# PCB2022-20-02.net
KiCad netlist of a schematic drawn in EAGLE
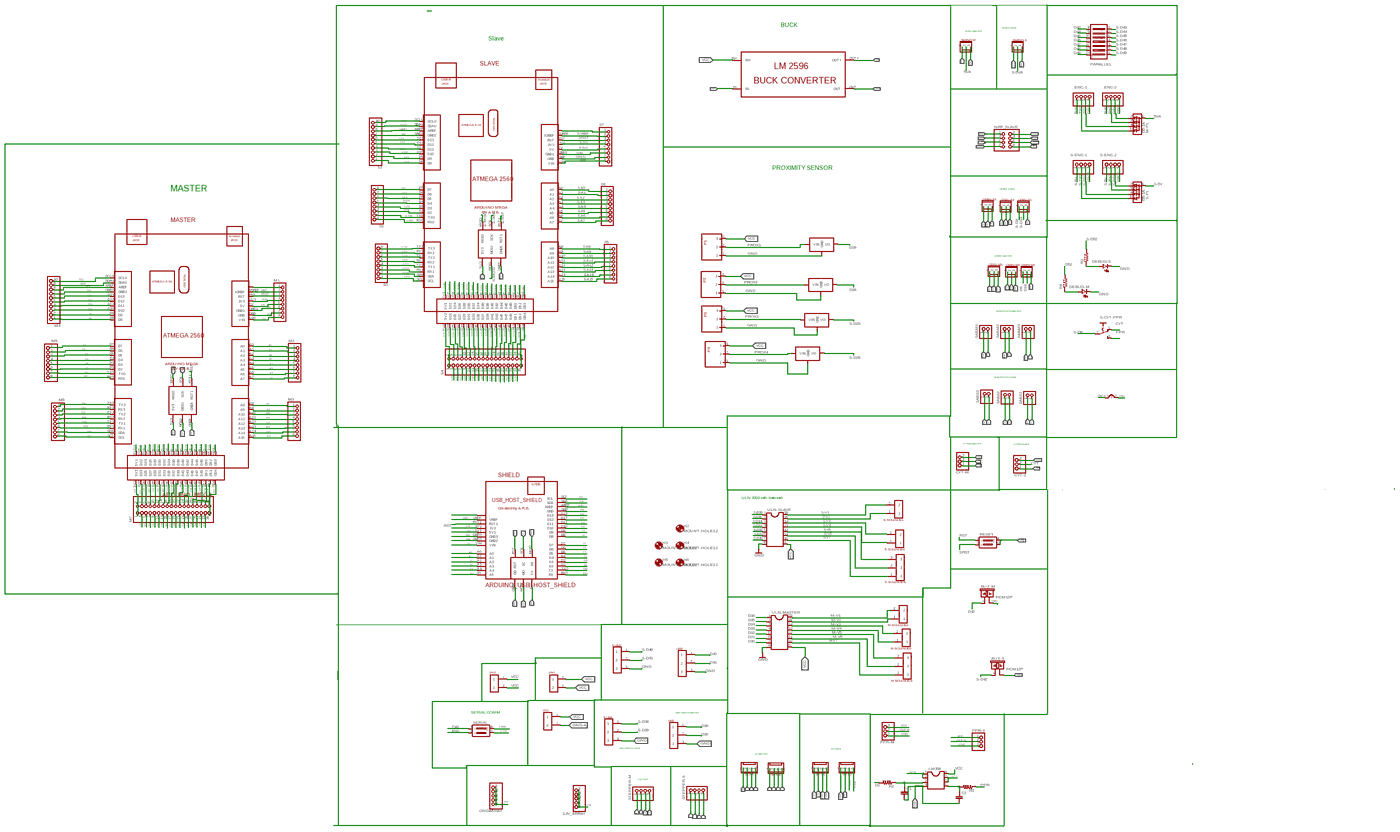
[diagram p0: schematic, sheet 1, overview]
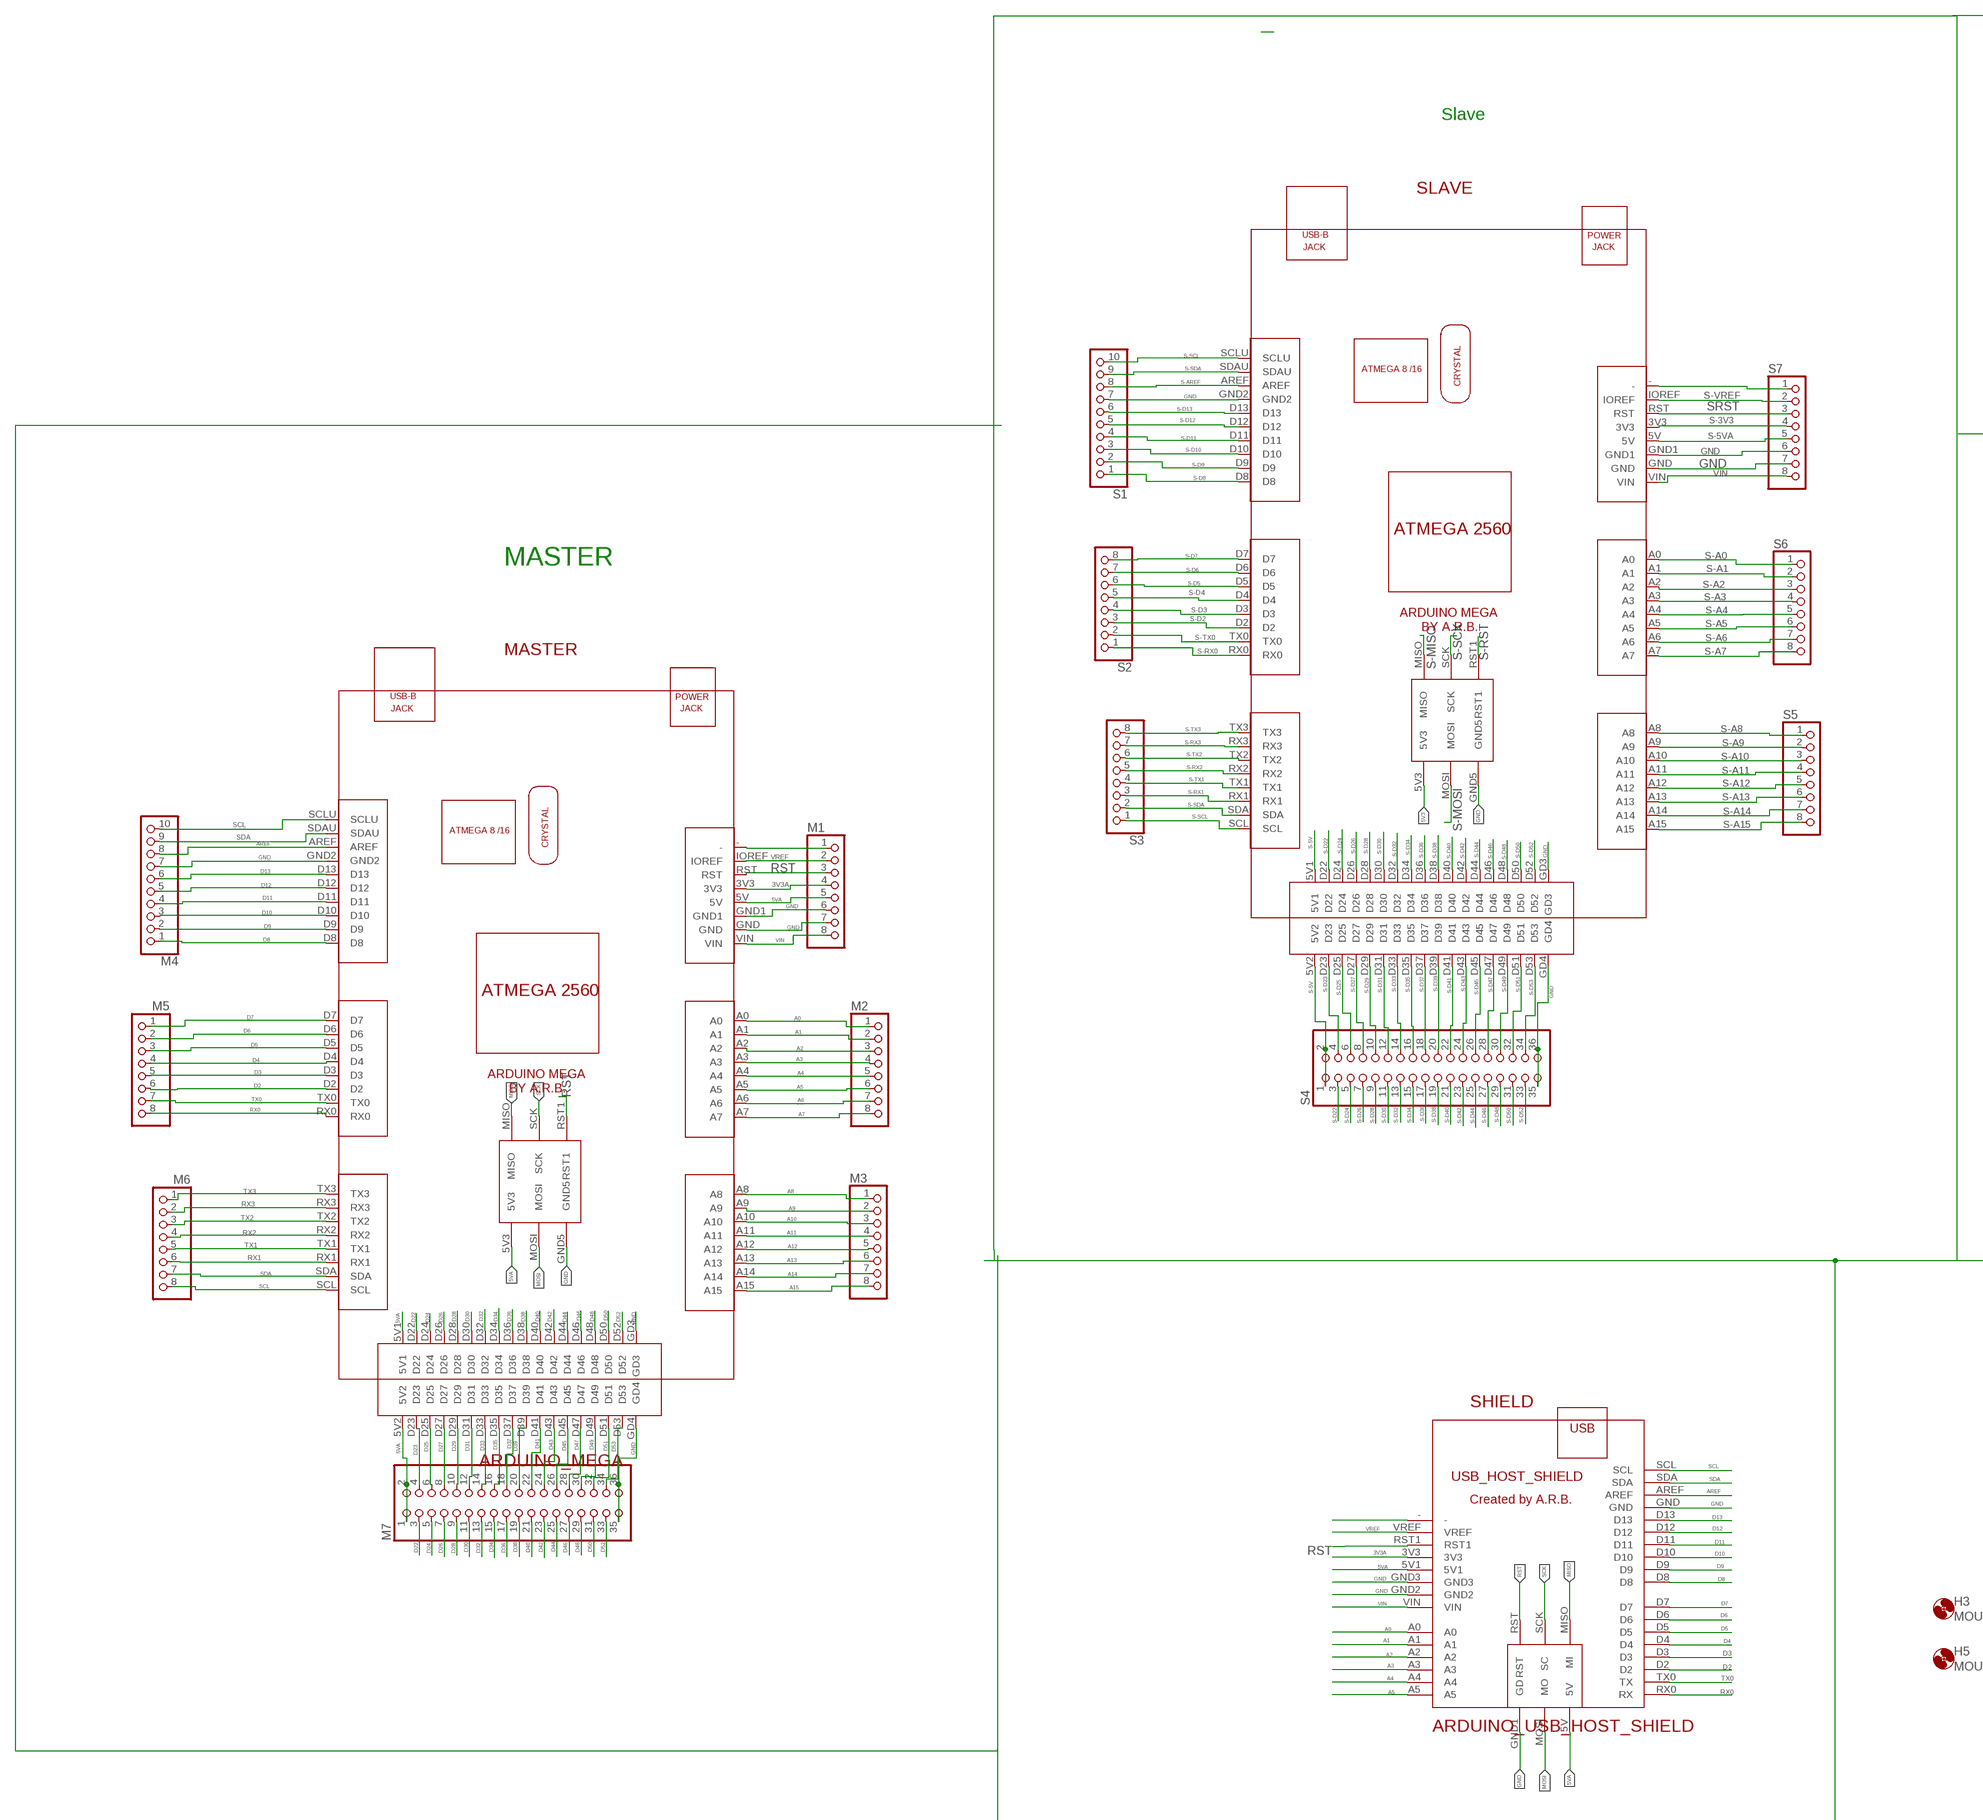
[diagram p1: schematic, sheet 1, part 1 of 4]
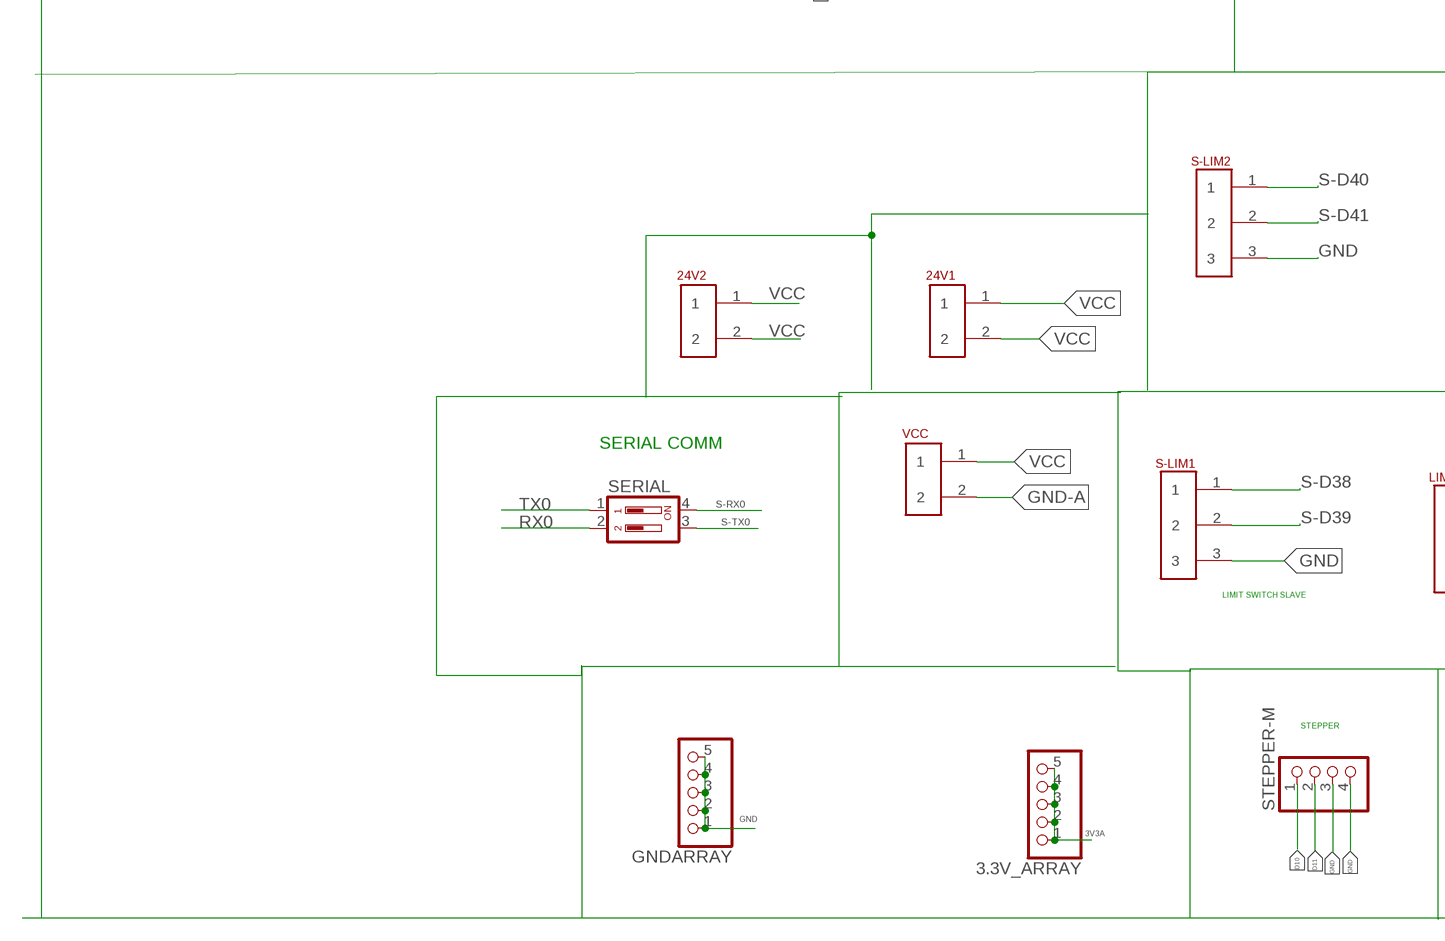
[diagram p2: schematic, sheet 1, part 2 of 4]
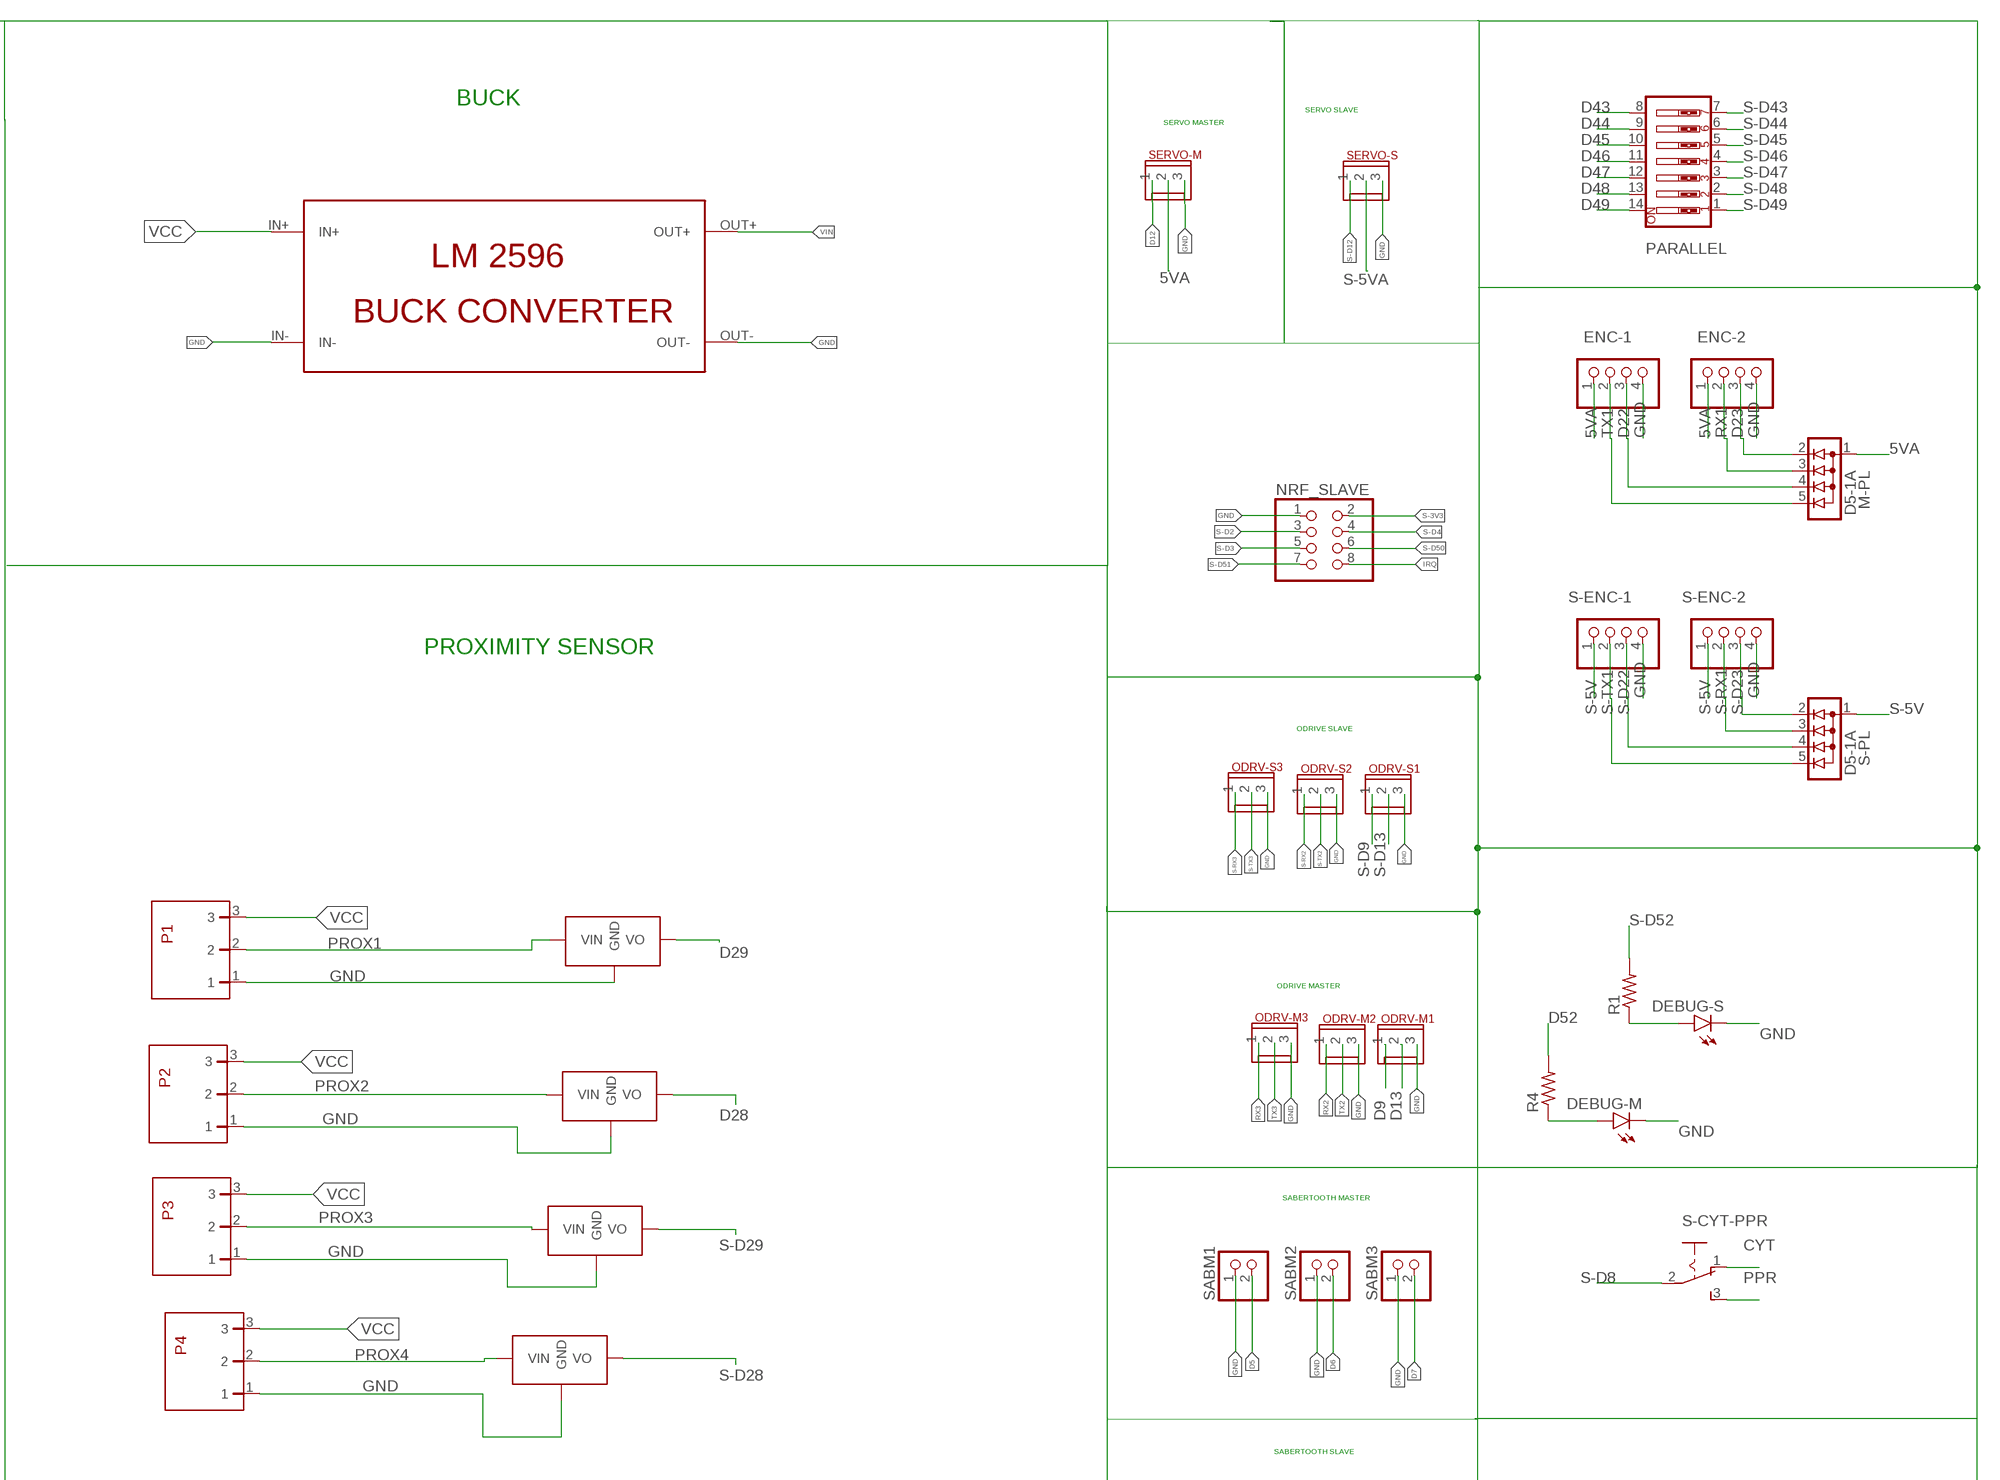
[diagram p3: schematic, sheet 1, part 3 of 4]
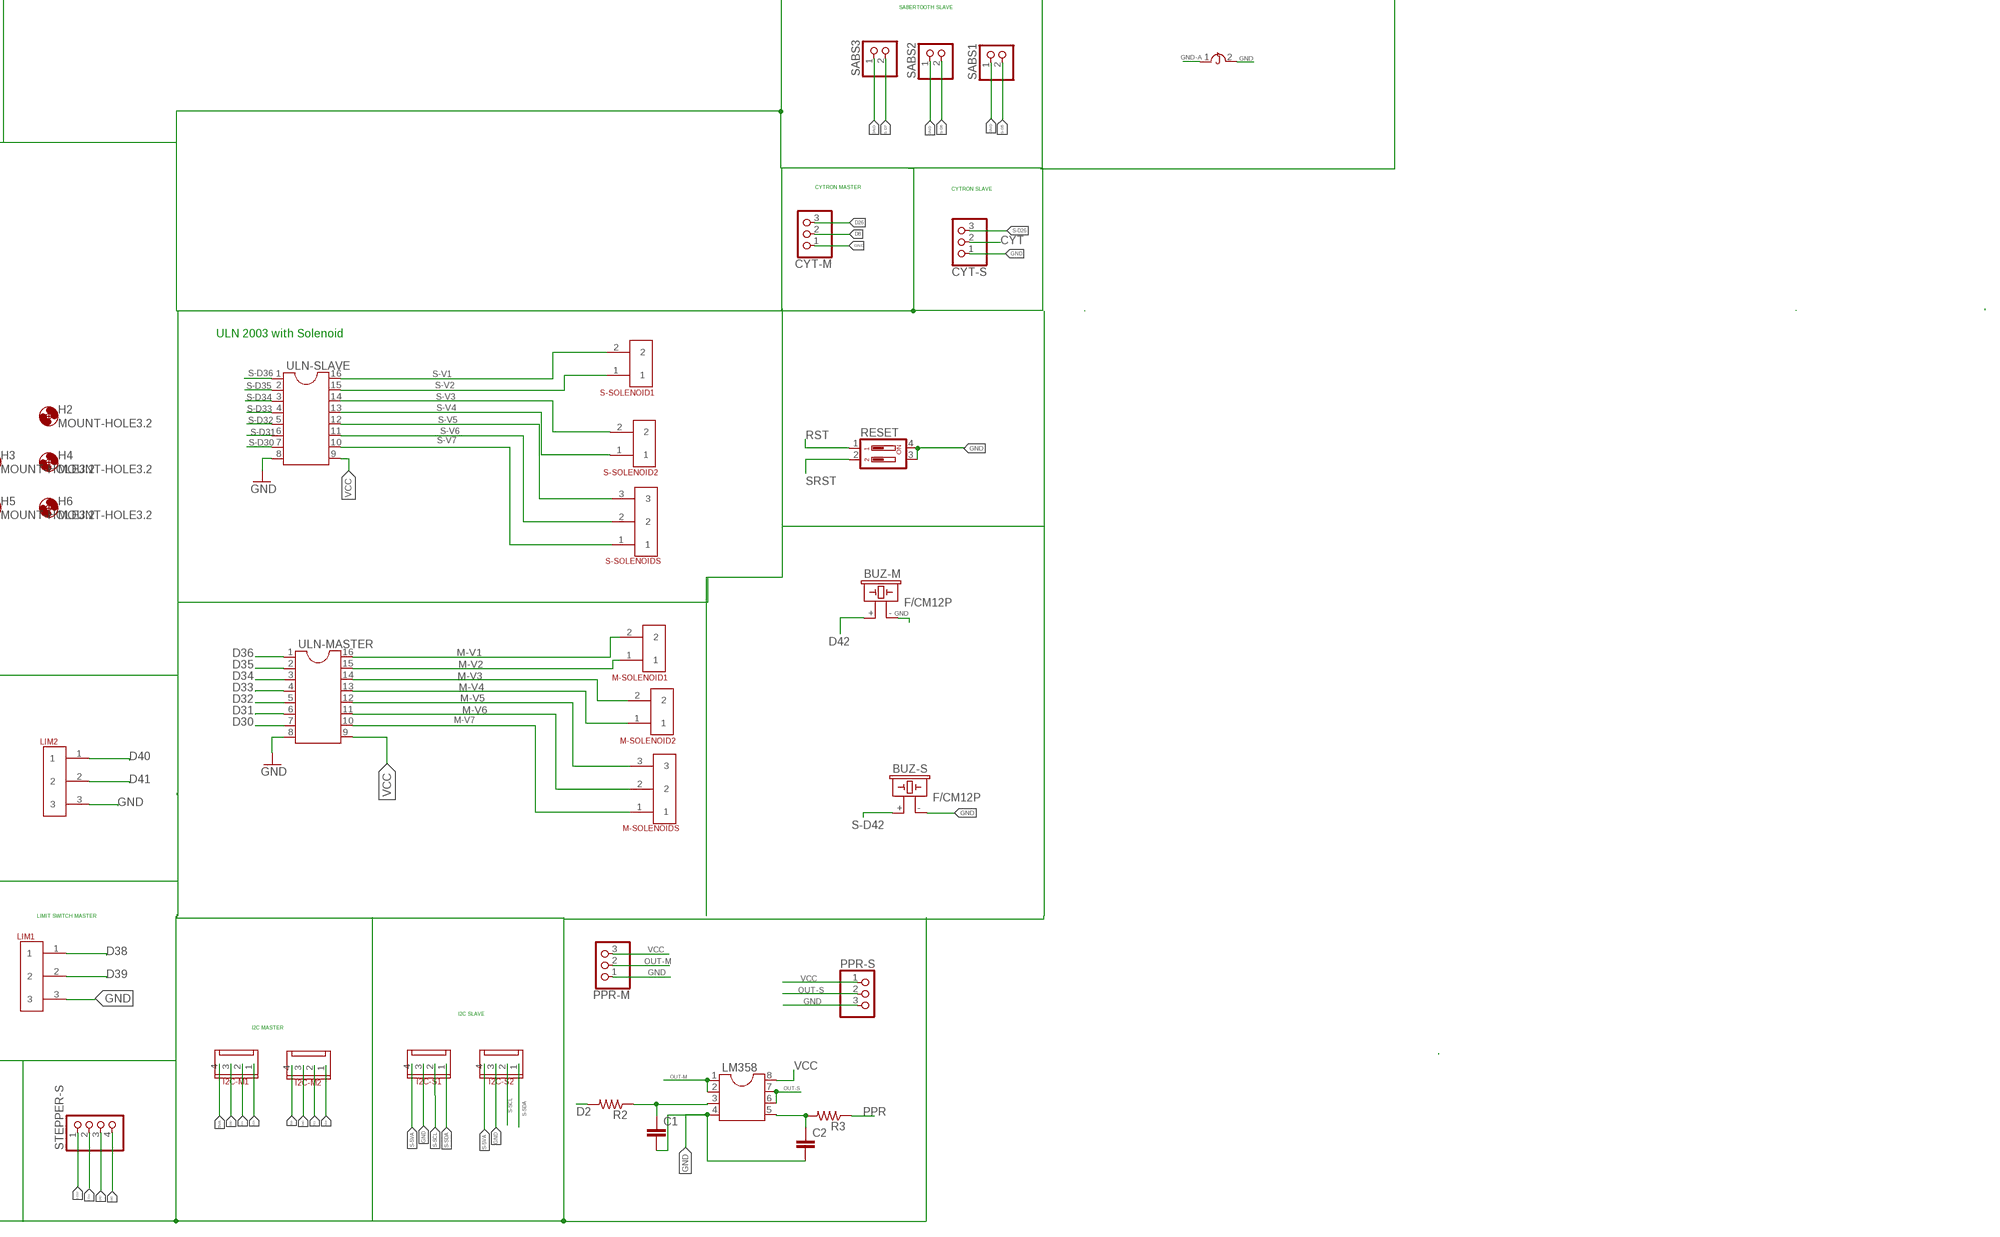
[diagram p4: schematic, sheet 1, part 4 of 4]

(export (version "E")
  (design (tool "Eeschema 10.0.6"))
  (components
    (comp (ref "3.3V_ARRAY")
      (value "PINHD-1X5")
      (footprint "eagle-import:1X05")
      (libsource (lib "eagle-import") (part "PINHD-1X5"))
    )
    (comp (ref "24V1")
      (value "AB_SCREW_TERMINAL_5MM_2PIN")
      (footprint "eagle-import:AB_SCREW_TERMINAL_5MM_2PIN")
      (libsource (lib "eagle-import") (part "AB_SCREW_TERMINAL_5MM_2PIN"))
    )
    (comp (ref "24V2")
      (value "AB_SCREW_TERMINAL_5MM_2PIN")
      (footprint "eagle-import:AB_SCREW_TERMINAL_5MM_2PIN")
      (libsource (lib "eagle-import") (part "AB_SCREW_TERMINAL_5MM_2PIN"))
    )
    (comp (ref "BUZ-M")
      (value "F/CM12P")
      (footprint "eagle-import:F_CM12P")
      (libsource (lib "eagle-import") (part "F/CM12P"))
    )
    (comp (ref "BUZ-S")
      (value "F/CM12P")
      (footprint "eagle-import:F_CM12P")
      (libsource (lib "eagle-import") (part "F/CM12P"))
    )
    (comp (ref "C1")
      (value "C-EU025-025X050")
      (footprint "eagle-import:C025-025X050")
      (libsource (lib "eagle-import") (part "C-EU025-025X050"))
    )
    (comp (ref "C2")
      (value "C-EU025-025X050")
      (footprint "eagle-import:C025-025X050")
      (libsource (lib "eagle-import") (part "C-EU025-025X050"))
    )
    (comp (ref "CYT-M")
      (value "PINHD-1X3")
      (footprint "eagle-import:1X03")
      (libsource (lib "eagle-import") (part "PINHD-1X3"))
    )
    (comp (ref "CYT-S")
      (value "PINHD-1X3")
      (footprint "eagle-import:1X03")
      (libsource (lib "eagle-import") (part "PINHD-1X3"))
    )
    (comp (ref "DEBUG-M")
      (value "LED5MM")
      (footprint "eagle-import:LED5MM")
      (libsource (lib "eagle-import") (part "LED5MM"))
    )
    (comp (ref "DEBUG-S")
      (value "LED5MM")
      (footprint "eagle-import:LED5MM")
      (libsource (lib "eagle-import") (part "LED5MM"))
    )
    (comp (ref "ENC-1")
      (value "PINHD-1X4")
      (footprint "eagle-import:1X04")
      (libsource (lib "eagle-import") (part "PINHD-1X4"))
    )
    (comp (ref "ENC-2")
      (value "PINHD-1X4")
      (footprint "eagle-import:1X04")
      (libsource (lib "eagle-import") (part "PINHD-1X4"))
    )
    (comp (ref "GNDARRAY")
      (value "PINHD-1X5")
      (footprint "eagle-import:1X05")
      (libsource (lib "eagle-import") (part "PINHD-1X5"))
    )
    (comp (ref "H2")
      (value "MOUNT-HOLE3.2")
      (footprint "eagle-import:3,2")
      (libsource (lib "eagle-import") (part "MOUNT-HOLE3.2"))
    )
    (comp (ref "H3")
      (value "MOUNT-HOLE3.2")
      (footprint "eagle-import:3,2")
      (libsource (lib "eagle-import") (part "MOUNT-HOLE3.2"))
    )
    (comp (ref "H4")
      (value "MOUNT-HOLE3.2")
      (footprint "eagle-import:3,2")
      (libsource (lib "eagle-import") (part "MOUNT-HOLE3.2"))
    )
    (comp (ref "H5")
      (value "MOUNT-HOLE3.2")
      (footprint "eagle-import:3,2")
      (libsource (lib "eagle-import") (part "MOUNT-HOLE3.2"))
    )
    (comp (ref "H6")
      (value "MOUNT-HOLE3.2")
      (footprint "eagle-import:3,2")
      (libsource (lib "eagle-import") (part "MOUNT-HOLE3.2"))
    )
    (comp (ref "I2C-M1")
      (value "4PIN_RELIMATE_CONNECTOR")
      (footprint "eagle-import:4PIN_RELIMATE_CONNECTOR")
      (libsource (lib "eagle-import") (part "4PIN_RELIMATE_CONNECTOR"))
    )
    (comp (ref "I2C-M2")
      (value "4PIN_RELIMATE_CONNECTOR")
      (footprint "eagle-import:4PIN_RELIMATE_CONNECTOR")
      (libsource (lib "eagle-import") (part "4PIN_RELIMATE_CONNECTOR"))
    )
    (comp (ref "I2C-S1")
      (value "4PIN_RELIMATE_CONNECTOR")
      (footprint "eagle-import:4PIN_RELIMATE_CONNECTOR")
      (libsource (lib "eagle-import") (part "4PIN_RELIMATE_CONNECTOR"))
    )
    (comp (ref "I2C-S2")
      (value "4PIN_RELIMATE_CONNECTOR")
      (footprint "eagle-import:4PIN_RELIMATE_CONNECTOR")
      (libsource (lib "eagle-import") (part "4PIN_RELIMATE_CONNECTOR"))
    )
    (comp (ref "LIM1")
      (value "AB_SCREW_TER_5MM_3PIN")
      (footprint "eagle-import:AB_SCREW_TER_5MM_3PIN")
      (libsource (lib "eagle-import") (part "AB_SCREW_TER_5MM_3PIN"))
    )
    (comp (ref "LIM2")
      (value "AB_SCREW_TER_5MM_3PIN")
      (footprint "eagle-import:AB_SCREW_TER_5MM_3PIN")
      (libsource (lib "eagle-import") (part "AB_SCREW_TER_5MM_3PIN"))
    )
    (comp (ref "LM358")
      (value "DIL8")
      (footprint "eagle-import:DIL08")
      (libsource (lib "eagle-import") (part "DIL8"))
    )
    (comp (ref "M-PL")
      (value "D5-1A")
      (footprint "eagle-import:SIL05A")
      (libsource (lib "eagle-import") (part "D5-1A"))
    )
    (comp (ref "M-SOLENOID1")
      (value "AB_SCREW_TERMINAL_5MM_2PIN")
      (footprint "eagle-import:AB_SCREW_TERMINAL_5MM_2PIN")
      (libsource (lib "eagle-import") (part "AB_SCREW_TERMINAL_5MM_2PIN"))
    )
    (comp (ref "M-SOLENOID2")
      (value "AB_SCREW_TERMINAL_5MM_2PIN")
      (footprint "eagle-import:AB_SCREW_TERMINAL_5MM_2PIN")
      (libsource (lib "eagle-import") (part "AB_SCREW_TERMINAL_5MM_2PIN"))
    )
    (comp (ref "M-SOLENOIDS")
      (value "AB_SCREW_TER_5MM_3PIN")
      (footprint "eagle-import:AB_SCREW_TER_5MM_3PIN")
      (libsource (lib "eagle-import") (part "AB_SCREW_TER_5MM_3PIN"))
    )
    (comp (ref "M1")
      (value "PINHD-1X8")
      (footprint "eagle-import:1X08")
      (libsource (lib "eagle-import") (part "PINHD-1X8"))
    )
    (comp (ref "M2")
      (value "PINHD-1X8")
      (footprint "eagle-import:1X08")
      (libsource (lib "eagle-import") (part "PINHD-1X8"))
    )
    (comp (ref "M3")
      (value "PINHD-1X8")
      (footprint "eagle-import:1X08")
      (libsource (lib "eagle-import") (part "PINHD-1X8"))
    )
    (comp (ref "M4")
      (value "PINHD-1X10")
      (footprint "eagle-import:1X10")
      (libsource (lib "eagle-import") (part "PINHD-1X10"))
    )
    (comp (ref "M5")
      (value "PINHD-1X8")
      (footprint "eagle-import:1X08")
      (libsource (lib "eagle-import") (part "PINHD-1X8"))
    )
    (comp (ref "M6")
      (value "PINHD-1X8")
      (footprint "eagle-import:1X08")
      (libsource (lib "eagle-import") (part "PINHD-1X8"))
    )
    (comp (ref "M7")
      (value "PINHD-2X18")
      (footprint "eagle-import:2X18")
      (libsource (lib "eagle-import") (part "PINHD-2X18"))
    )
    (comp (ref "MASTER")
      (value "ARDUINO_MEGA")
      (footprint "eagle-import:ARDUINO_MEGA")
      (libsource (lib "eagle-import") (part "ARDUINO_MEGA"))
    )
    (comp (ref "NRF_SLAVE")
      (value "PINHD-2X4")
      (footprint "eagle-import:2X04")
      (libsource (lib "eagle-import") (part "PINHD-2X4"))
    )
    (comp (ref "ODRV-M1")
      (value "3PIN_RELIMATE_CONNECTOR")
      (footprint "eagle-import:3PIN_RELIMATE_CONNECTOR")
      (libsource (lib "eagle-import") (part "3PIN_RELIMATE_CONNECTOR"))
    )
    (comp (ref "ODRV-M2")
      (value "3PIN_RELIMATE_CONNECTOR")
      (footprint "eagle-import:3PIN_RELIMATE_CONNECTOR")
      (libsource (lib "eagle-import") (part "3PIN_RELIMATE_CONNECTOR"))
    )
    (comp (ref "ODRV-M3")
      (value "3PIN_RELIMATE_CONNECTOR")
      (footprint "eagle-import:3PIN_RELIMATE_CONNECTOR")
      (libsource (lib "eagle-import") (part "3PIN_RELIMATE_CONNECTOR"))
    )
    (comp (ref "ODRV-S1")
      (value "3PIN_RELIMATE_CONNECTOR")
      (footprint "eagle-import:3PIN_RELIMATE_CONNECTOR")
      (libsource (lib "eagle-import") (part "3PIN_RELIMATE_CONNECTOR"))
    )
    (comp (ref "ODRV-S2")
      (value "3PIN_RELIMATE_CONNECTOR")
      (footprint "eagle-import:3PIN_RELIMATE_CONNECTOR")
      (libsource (lib "eagle-import") (part "3PIN_RELIMATE_CONNECTOR"))
    )
    (comp (ref "ODRV-S3")
      (value "3PIN_RELIMATE_CONNECTOR")
      (footprint "eagle-import:3PIN_RELIMATE_CONNECTOR")
      (libsource (lib "eagle-import") (part "3PIN_RELIMATE_CONNECTOR"))
    )
    (comp (ref "P1")
      (value "AB_RIGHT_TER_BLK_3PIN")
      (footprint "eagle-import:AB_RIGHT_TER_BLK_3PIN")
      (libsource (lib "eagle-import") (part "AB_RIGHT_TER_BLK_3PIN"))
    )
    (comp (ref "P2")
      (value "AB_RIGHT_TER_BLK_3PIN")
      (footprint "eagle-import:AB_RIGHT_TER_BLK_3PIN")
      (libsource (lib "eagle-import") (part "AB_RIGHT_TER_BLK_3PIN"))
    )
    (comp (ref "P3")
      (value "AB_RIGHT_TER_BLK_3PIN")
      (footprint "eagle-import:AB_RIGHT_TER_BLK_3PIN")
      (libsource (lib "eagle-import") (part "AB_RIGHT_TER_BLK_3PIN"))
    )
    (comp (ref "P4")
      (value "AB_RIGHT_TER_BLK_3PIN")
      (footprint "eagle-import:AB_RIGHT_TER_BLK_3PIN")
      (libsource (lib "eagle-import") (part "AB_RIGHT_TER_BLK_3PIN"))
    )
    (comp (ref "PARALLEL")
      (value "SW_DIP-7")
      (footprint "eagle-import:EDG-07")
      (libsource (lib "eagle-import") (part "SW_DIP-7"))
    )
    (comp (ref "PPR-M")
      (value "PINHD-1X3")
      (footprint "eagle-import:1X03")
      (libsource (lib "eagle-import") (part "PINHD-1X3"))
    )
    (comp (ref "PPR-S")
      (value "PINHD-1X3")
      (footprint "eagle-import:1X03")
      (libsource (lib "eagle-import") (part "PINHD-1X3"))
    )
    (comp (ref "R1")
      (value "R-US_0204/5")
      (footprint "eagle-import:0204_5")
      (libsource (lib "eagle-import") (part "R-US_0204/5"))
    )
    (comp (ref "R2")
      (value "R-US_0204/5")
      (footprint "eagle-import:0204_5")
      (libsource (lib "eagle-import") (part "R-US_0204/5"))
    )
    (comp (ref "R3")
      (value "R-US_0204/5")
      (footprint "eagle-import:0204_5")
      (libsource (lib "eagle-import") (part "R-US_0204/5"))
    )
    (comp (ref "R4")
      (value "R-US_0204/5")
      (footprint "eagle-import:0204_5")
      (libsource (lib "eagle-import") (part "R-US_0204/5"))
    )
    (comp (ref "RESET")
      (value "DIP02YL")
      (footprint "eagle-import:DIP02YL")
      (libsource (lib "eagle-import") (part "DIP02YL"))
    )
    (comp (ref "S-CYT-PPR")
      (value "255SB")
      (footprint "eagle-import:255SB")
      (libsource (lib "eagle-import") (part "255SB"))
    )
    (comp (ref "S-ENC-1")
      (value "PINHD-1X4")
      (footprint "eagle-import:1X04")
      (libsource (lib "eagle-import") (part "PINHD-1X4"))
    )
    (comp (ref "S-ENC-2")
      (value "PINHD-1X4")
      (footprint "eagle-import:1X04")
      (libsource (lib "eagle-import") (part "PINHD-1X4"))
    )
    (comp (ref "S-LIM1")
      (value "AB_SCREW_TER_5MM_3PIN")
      (footprint "eagle-import:AB_SCREW_TER_5MM_3PIN")
      (libsource (lib "eagle-import") (part "AB_SCREW_TER_5MM_3PIN"))
    )
    (comp (ref "S-LIM2")
      (value "AB_SCREW_TER_5MM_3PIN")
      (footprint "eagle-import:AB_SCREW_TER_5MM_3PIN")
      (libsource (lib "eagle-import") (part "AB_SCREW_TER_5MM_3PIN"))
    )
    (comp (ref "S-PL")
      (value "D5-1A")
      (footprint "eagle-import:SIL05A")
      (libsource (lib "eagle-import") (part "D5-1A"))
    )
    (comp (ref "S-SOLENOID1")
      (value "AB_SCREW_TERMINAL_5MM_2PIN")
      (footprint "eagle-import:AB_SCREW_TERMINAL_5MM_2PIN")
      (libsource (lib "eagle-import") (part "AB_SCREW_TERMINAL_5MM_2PIN"))
    )
    (comp (ref "S-SOLENOID2")
      (value "AB_SCREW_TERMINAL_5MM_2PIN")
      (footprint "eagle-import:AB_SCREW_TERMINAL_5MM_2PIN")
      (libsource (lib "eagle-import") (part "AB_SCREW_TERMINAL_5MM_2PIN"))
    )
    (comp (ref "S-SOLENOIDS")
      (value "AB_SCREW_TER_5MM_3PIN")
      (footprint "eagle-import:AB_SCREW_TER_5MM_3PIN")
      (libsource (lib "eagle-import") (part "AB_SCREW_TER_5MM_3PIN"))
    )
    (comp (ref "S1")
      (value "PINHD-1X10")
      (footprint "eagle-import:1X10")
      (libsource (lib "eagle-import") (part "PINHD-1X10"))
    )
    (comp (ref "S2")
      (value "PINHD-1X8")
      (footprint "eagle-import:1X08")
      (libsource (lib "eagle-import") (part "PINHD-1X8"))
    )
    (comp (ref "S3")
      (value "PINHD-1X8")
      (footprint "eagle-import:1X08")
      (libsource (lib "eagle-import") (part "PINHD-1X8"))
    )
    (comp (ref "S4")
      (value "PINHD-2X18")
      (footprint "eagle-import:2X18")
      (libsource (lib "eagle-import") (part "PINHD-2X18"))
    )
    (comp (ref "S5")
      (value "PINHD-1X8")
      (footprint "eagle-import:1X08")
      (libsource (lib "eagle-import") (part "PINHD-1X8"))
    )
    (comp (ref "S6")
      (value "PINHD-1X8")
      (footprint "eagle-import:1X08")
      (libsource (lib "eagle-import") (part "PINHD-1X8"))
    )
    (comp (ref "S7")
      (value "PINHD-1X8")
      (footprint "eagle-import:1X08")
      (libsource (lib "eagle-import") (part "PINHD-1X8"))
    )
    (comp (ref "SABM1")
      (value "PINHD-1X2")
      (footprint "eagle-import:1X02")
      (fields (field (name "SPICEPREFIX") "B"))
      (libsource (lib "eagle-import") (part "PINHD-1X2"))
    )
    (comp (ref "SABM2")
      (value "PINHD-1X2")
      (footprint "eagle-import:1X02")
      (libsource (lib "eagle-import") (part "PINHD-1X2"))
    )
    (comp (ref "SABM3")
      (value "PINHD-1X2")
      (footprint "eagle-import:1X02")
      (libsource (lib "eagle-import") (part "PINHD-1X2"))
    )
    (comp (ref "SABS1")
      (value "PINHD-1X2")
      (footprint "eagle-import:1X02")
      (libsource (lib "eagle-import") (part "PINHD-1X2"))
    )
    (comp (ref "SABS2")
      (value "PINHD-1X2")
      (footprint "eagle-import:1X02")
      (libsource (lib "eagle-import") (part "PINHD-1X2"))
    )
    (comp (ref "SABS3")
      (value "PINHD-1X2")
      (footprint "eagle-import:1X02")
      (libsource (lib "eagle-import") (part "PINHD-1X2"))
    )
    (comp (ref "SERIAL")
      (value "DIP02YL")
      (footprint "eagle-import:DIP02YL")
      (libsource (lib "eagle-import") (part "DIP02YL"))
    )
    (comp (ref "SERVO-M")
      (value "3PIN_RELIMATE_CONNECTOR")
      (footprint "eagle-import:3PIN_RELIMATE_CONNECTOR")
      (libsource (lib "eagle-import") (part "3PIN_RELIMATE_CONNECTOR"))
    )
    (comp (ref "SERVO-S")
      (value "3PIN_RELIMATE_CONNECTOR")
      (footprint "eagle-import:3PIN_RELIMATE_CONNECTOR")
      (libsource (lib "eagle-import") (part "3PIN_RELIMATE_CONNECTOR"))
    )
    (comp (ref "SHIELD")
      (value "ARDUINO_USB_HOST_SHIELD")
      (footprint "eagle-import:ARDUINO_USB_HOST_SHIELD")
      (libsource (lib "eagle-import") (part "ARDUINO_USB_HOST_SHIELD"))
    )
    (comp (ref "SLAVE")
      (value "ARDUINO_MEGA")
      (footprint "eagle-import:ARDUINO_MEGA")
      (libsource (lib "eagle-import") (part "ARDUINO_MEGA"))
    )
    (comp (ref "STEPPER-M")
      (value "PINHD-1X4")
      (footprint "eagle-import:1X04")
      (libsource (lib "eagle-import") (part "PINHD-1X4"))
    )
    (comp (ref "STEPPER-S")
      (value "PINHD-1X4")
      (footprint "eagle-import:1X04")
      (libsource (lib "eagle-import") (part "PINHD-1X4"))
    )
    (comp (ref "U$2")
      (value "AB_JUMPER_ONE_WAY")
      (footprint "eagle-import:AB_JUMPER_ONE_WAY")
      (libsource (lib "eagle-import") (part "AB_JUMPER_ONE_WAY"))
    )
    (comp (ref "U$3")
      (value "LM2596_BUCK_CONVERTER")
      (footprint "eagle-import:LM2596_BUCK_CONVERTER")
      (libsource (lib "eagle-import") (part "LM2596_BUCK_CONVERTER"))
    )
    (comp (ref "U$10")
      (value "AB_7805_FLAT")
      (footprint "eagle-import:AB_7805_FLAT")
      (libsource (lib "eagle-import") (part "AB_7805_FLAT"))
    )
    (comp (ref "U$11")
      (value "AB_7805_FLAT")
      (footprint "eagle-import:AB_7805_FLAT")
      (libsource (lib "eagle-import") (part "AB_7805_FLAT"))
    )
    (comp (ref "U$12")
      (value "AB_7805_FLAT")
      (footprint "eagle-import:AB_7805_FLAT")
      (libsource (lib "eagle-import") (part "AB_7805_FLAT"))
    )
    (comp (ref "U$13")
      (value "AB_7805_FLAT")
      (footprint "eagle-import:AB_7805_FLAT")
      (libsource (lib "eagle-import") (part "AB_7805_FLAT"))
    )
    (comp (ref "ULN-MASTER")
      (value "DIL16")
      (footprint "eagle-import:DIL16")
      (libsource (lib "eagle-import") (part "DIL16"))
    )
    (comp (ref "ULN-SLAVE")
      (value "DIL16")
      (footprint "eagle-import:DIL16")
      (libsource (lib "eagle-import") (part "DIL16"))
    )
    (comp (ref "VCC")
      (value "AB_SCREW_TERMINAL_5MM_2PIN")
      (footprint "eagle-import:AB_SCREW_TERMINAL_5MM_2PIN")
      (libsource (lib "eagle-import") (part "AB_SCREW_TERMINAL_5MM_2PIN"))
    )
  )
  (nets
    (net (code "1") (name "/3V3A") (class "Default")
      (node (ref "3.3V_ARRAY") (pin "1") (pinfunction "1_1") (pintype "passive"))
      (node (ref "3.3V_ARRAY") (pin "2") (pinfunction "2_2") (pintype "passive"))
      (node (ref "3.3V_ARRAY") (pin "3") (pinfunction "3_3") (pintype "passive"))
      (node (ref "3.3V_ARRAY") (pin "4") (pinfunction "4_4") (pintype "passive"))
      (node (ref "3.3V_ARRAY") (pin "5") (pinfunction "5_5") (pintype "passive"))
      (node (ref "M1") (pin "4") (pinfunction "4_4") (pintype "passive"))
      (node (ref "MASTER") (pin "3V3") (pinfunction "3V3_3V3") (pintype "bidirectional"))
      (node (ref "SHIELD") (pin "3V3") (pinfunction "3V3_3V3") (pintype "bidirectional"))
    )
    (net (code "2") (name "/A0") (class "Default")
      (node (ref "M2") (pin "1") (pinfunction "1_1") (pintype "passive"))
      (node (ref "MASTER") (pin "A0") (pinfunction "A0_A0") (pintype "bidirectional"))
      (node (ref "SHIELD") (pin "A0") (pinfunction "A0_A0") (pintype "bidirectional"))
    )
    (net (code "3") (name "/A1") (class "Default")
      (node (ref "M2") (pin "2") (pinfunction "2_2") (pintype "passive"))
      (node (ref "MASTER") (pin "A1") (pinfunction "A1_A1") (pintype "bidirectional"))
      (node (ref "SHIELD") (pin "A1") (pinfunction "A1_A1") (pintype "bidirectional"))
    )
    (net (code "4") (name "/A2") (class "Default")
      (node (ref "M2") (pin "3") (pinfunction "3_3") (pintype "passive"))
      (node (ref "MASTER") (pin "A2") (pinfunction "A2_A2") (pintype "bidirectional"))
      (node (ref "SHIELD") (pin "A2") (pinfunction "A2_A2") (pintype "bidirectional"))
    )
    (net (code "5") (name "/A3") (class "Default")
      (node (ref "M2") (pin "4") (pinfunction "4_4") (pintype "passive"))
      (node (ref "MASTER") (pin "A3") (pinfunction "A3_A3") (pintype "bidirectional"))
      (node (ref "SHIELD") (pin "A3") (pinfunction "A3_A3") (pintype "bidirectional"))
    )
    (net (code "6") (name "/A4") (class "Default")
      (node (ref "M2") (pin "5") (pinfunction "5_5") (pintype "passive"))
      (node (ref "MASTER") (pin "A4") (pinfunction "A4_A4") (pintype "bidirectional"))
      (node (ref "SHIELD") (pin "A4") (pinfunction "A4_A4") (pintype "bidirectional"))
    )
    (net (code "7") (name "/A5") (class "Default")
      (node (ref "M2") (pin "6") (pinfunction "6_6") (pintype "passive"))
      (node (ref "MASTER") (pin "A5") (pinfunction "A5_A5") (pintype "bidirectional"))
      (node (ref "SHIELD") (pin "A5") (pinfunction "A5_A5") (pintype "bidirectional"))
    )
    (net (code "8") (name "/A6") (class "Default")
      (node (ref "M2") (pin "7") (pinfunction "7_7") (pintype "passive"))
      (node (ref "MASTER") (pin "A6") (pinfunction "A6_A6") (pintype "bidirectional"))
    )
    (net (code "9") (name "/A7") (class "Default")
      (node (ref "M2") (pin "8") (pinfunction "8_8") (pintype "passive"))
      (node (ref "MASTER") (pin "A7") (pinfunction "A7_A7") (pintype "bidirectional"))
    )
    (net (code "10") (name "/A8") (class "Default")
      (node (ref "M3") (pin "1") (pinfunction "1_1") (pintype "passive"))
      (node (ref "MASTER") (pin "A8") (pinfunction "A8_A8") (pintype "bidirectional"))
    )
    (net (code "11") (name "/A9") (class "Default")
      (node (ref "M3") (pin "2") (pinfunction "2_2") (pintype "passive"))
      (node (ref "MASTER") (pin "A9") (pinfunction "A9_A9") (pintype "bidirectional"))
    )
    (net (code "12") (name "/A10") (class "Default")
      (node (ref "M3") (pin "3") (pinfunction "3_3") (pintype "passive"))
      (node (ref "MASTER") (pin "A10") (pinfunction "A10_A10") (pintype "bidirectional"))
    )
    (net (code "13") (name "/A11") (class "Default")
      (node (ref "M3") (pin "4") (pinfunction "4_4") (pintype "passive"))
      (node (ref "MASTER") (pin "A11") (pinfunction "A11_A11") (pintype "bidirectional"))
    )
    (net (code "14") (name "/A12") (class "Default")
      (node (ref "M3") (pin "5") (pinfunction "5_5") (pintype "passive"))
      (node (ref "MASTER") (pin "A12") (pinfunction "A12_A12") (pintype "bidirectional"))
    )
    (net (code "15") (name "/A13") (class "Default")
      (node (ref "M3") (pin "6") (pinfunction "6_6") (pintype "passive"))
      (node (ref "MASTER") (pin "A13") (pinfunction "A13_A13") (pintype "bidirectional"))
    )
    (net (code "16") (name "/A14") (class "Default")
      (node (ref "M3") (pin "7") (pinfunction "7_7") (pintype "passive"))
      (node (ref "MASTER") (pin "A14") (pinfunction "A14_A14") (pintype "bidirectional"))
    )
    (net (code "17") (name "/A15") (class "Default")
      (node (ref "M3") (pin "8") (pinfunction "8_8") (pintype "passive"))
      (node (ref "MASTER") (pin "A15") (pinfunction "A15_A15") (pintype "bidirectional"))
    )
    (net (code "18") (name "/AREF") (class "Default")
      (node (ref "M4") (pin "8") (pinfunction "8_8") (pintype "passive"))
      (node (ref "MASTER") (pin "AREF") (pinfunction "AREF_AREF") (pintype "bidirectional"))
      (node (ref "SHIELD") (pin "AREF") (pinfunction "AREF_AREF") (pintype "bidirectional"))
    )
    (net (code "19") (name "/CYT") (class "Default")
      (node (ref "CYT-S") (pin "2") (pinfunction "2_2") (pintype "passive"))
      (node (ref "S-CYT-PPR") (pin "1") (pinfunction "O_1") (pintype "passive"))
    )
    (net (code "20") (name "/D2") (class "Default")
      (node (ref "M5") (pin "6") (pinfunction "6_6") (pintype "passive"))
      (node (ref "MASTER") (pin "D2") (pinfunction "D2_D2") (pintype "bidirectional"))
      (node (ref "R2") (pin "2") (pinfunction "2_2") (pintype "passive"))
      (node (ref "SHIELD") (pin "D2") (pinfunction "D2_D2") (pintype "bidirectional"))
    )
    (net (code "21") (name "/D3") (class "Default")
      (node (ref "M5") (pin "5") (pinfunction "5_5") (pintype "passive"))
      (node (ref "MASTER") (pin "D3") (pinfunction "D3_D3") (pintype "bidirectional"))
      (node (ref "SHIELD") (pin "D3") (pinfunction "D3_D3") (pintype "bidirectional"))
    )
    (net (code "22") (name "/D4") (class "Default")
      (node (ref "M5") (pin "4") (pinfunction "4_4") (pintype "passive"))
      (node (ref "MASTER") (pin "D4") (pinfunction "D4_D4") (pintype "bidirectional"))
      (node (ref "SHIELD") (pin "D4") (pinfunction "D4_D4") (pintype "bidirectional"))
    )
    (net (code "23") (name "/D9") (class "Default")
      (node (ref "M4") (pin "2") (pinfunction "2_2") (pintype "passive"))
      (node (ref "MASTER") (pin "D9") (pinfunction "D9_D9") (pintype "bidirectional"))
      (node (ref "ODRV-M1") (pin "1") (pinfunction "1_1") (pintype "bidirectional"))
      (node (ref "SHIELD") (pin "D9") (pinfunction "D9_D9") (pintype "bidirectional"))
    )
    (net (code "24") (name "/D13") (class "Default")
      (node (ref "M4") (pin "6") (pinfunction "6_6") (pintype "passive"))
      (node (ref "MASTER") (pin "D13") (pinfunction "D13_D13") (pintype "bidirectional"))
      (node (ref "ODRV-M1") (pin "2") (pinfunction "2_2") (pintype "bidirectional"))
      (node (ref "SHIELD") (pin "D13") (pinfunction "D13_D13") (pintype "bidirectional"))
    )
    (net (code "25") (name "/D22") (class "Default")
      (node (ref "ENC-1") (pin "3") (pinfunction "3_3") (pintype "passive"))
      (node (ref "M-PL") (pin "4") (pinfunction "C4_4") (pintype "passive"))
      (node (ref "M7") (pin "3") (pinfunction "3_3") (pintype "passive"))
      (node (ref "MASTER") (pin "D22") (pinfunction "D22_D22") (pintype "bidirectional"))
    )
    (net (code "26") (name "/D23") (class "Default")
      (node (ref "ENC-2") (pin "3") (pinfunction "3_3") (pintype "passive"))
      (node (ref "M-PL") (pin "2") (pinfunction "C2_2") (pintype "passive"))
      (node (ref "M7") (pin "4") (pinfunction "4_4") (pintype "passive"))
      (node (ref "MASTER") (pin "D23") (pinfunction "D23_D23") (pintype "bidirectional"))
    )
    (net (code "27") (name "/D24") (class "Default")
      (node (ref "M7") (pin "5") (pinfunction "5_5") (pintype "passive"))
      (node (ref "MASTER") (pin "D24") (pinfunction "D24_D24") (pintype "bidirectional"))
    )
    (net (code "28") (name "/D25") (class "Default")
      (node (ref "M7") (pin "6") (pinfunction "6_6") (pintype "passive"))
      (node (ref "MASTER") (pin "D25") (pinfunction "D25_D25") (pintype "bidirectional"))
    )
    (net (code "29") (name "/D27") (class "Default")
      (node (ref "M7") (pin "8") (pinfunction "8_8") (pintype "passive"))
      (node (ref "MASTER") (pin "D27") (pinfunction "D27_D27") (pintype "bidirectional"))
    )
    (net (code "30") (name "/D28") (class "Default")
      (node (ref "M7") (pin "9") (pinfunction "9_9") (pintype "passive"))
      (node (ref "MASTER") (pin "D28") (pinfunction "D28_D28") (pintype "bidirectional"))
      (node (ref "U$11") (pin "3") (pinfunction "VO_3") (pintype "bidirectional"))
    )
    (net (code "31") (name "/D29") (class "Default")
      (node (ref "M7") (pin "10") (pinfunction "10_10") (pintype "passive"))
      (node (ref "MASTER") (pin "D29") (pinfunction "D29_D29") (pintype "bidirectional"))
      (node (ref "U$10") (pin "3") (pinfunction "VO_3") (pintype "bidirectional"))
    )
    (net (code "32") (name "/D30") (class "Default")
      (node (ref "M7") (pin "11") (pinfunction "11_11") (pintype "passive"))
      (node (ref "MASTER") (pin "D30") (pinfunction "D30_D30") (pintype "bidirectional"))
      (node (ref "ULN-MASTER") (pin "7") (pinfunction "7_7") (pintype "passive"))
    )
    (net (code "33") (name "/D31") (class "Default")
      (node (ref "M7") (pin "12") (pinfunction "12_12") (pintype "passive"))
      (node (ref "MASTER") (pin "D31") (pinfunction "D31_D31") (pintype "bidirectional"))
      (node (ref "ULN-MASTER") (pin "6") (pinfunction "6_6") (pintype "passive"))
    )
    (net (code "34") (name "/D32") (class "Default")
      (node (ref "M7") (pin "13") (pinfunction "13_13") (pintype "passive"))
      (node (ref "MASTER") (pin "D32") (pinfunction "D32_D32") (pintype "bidirectional"))
      (node (ref "ULN-MASTER") (pin "5") (pinfunction "5_5") (pintype "passive"))
    )
    (net (code "35") (name "/D33") (class "Default")
      (node (ref "M7") (pin "14") (pinfunction "14_14") (pintype "passive"))
      (node (ref "MASTER") (pin "D33") (pinfunction "D33_D33") (pintype "bidirectional"))
      (node (ref "ULN-MASTER") (pin "4") (pinfunction "4_4") (pintype "passive"))
    )
    (net (code "36") (name "/D34") (class "Default")
      (node (ref "M7") (pin "15") (pinfunction "15_15") (pintype "passive"))
      (node (ref "MASTER") (pin "D34") (pinfunction "D34_D34") (pintype "bidirectional"))
      (node (ref "ULN-MASTER") (pin "3") (pinfunction "3_3") (pintype "passive"))
    )
    (net (code "37") (name "/D35") (class "Default")
      (node (ref "M7") (pin "16") (pinfunction "16_16") (pintype "passive"))
      (node (ref "MASTER") (pin "D35") (pinfunction "D35_D35") (pintype "bidirectional"))
      (node (ref "ULN-MASTER") (pin "2") (pinfunction "2_2") (pintype "passive"))
    )
    (net (code "38") (name "/D36") (class "Default")
      (node (ref "M7") (pin "17") (pinfunction "17_17") (pintype "passive"))
      (node (ref "MASTER") (pin "D36") (pinfunction "D36_D36") (pintype "bidirectional"))
      (node (ref "ULN-MASTER") (pin "1") (pinfunction "1_1") (pintype "passive"))
    )
    (net (code "39") (name "/D37") (class "Default")
      (node (ref "M7") (pin "18") (pinfunction "18_18") (pintype "passive"))
      (node (ref "MASTER") (pin "D37") (pinfunction "D37_D37") (pintype "bidirectional"))
    )
    (net (code "40") (name "/D38") (class "Default")
      (node (ref "LIM1") (pin "1") (pinfunction "1_1") (pintype "bidirectional"))
      (node (ref "M7") (pin "19") (pinfunction "19_19") (pintype "passive"))
      (node (ref "MASTER") (pin "D38") (pinfunction "D38_D38") (pintype "bidirectional"))
    )
    (net (code "41") (name "/D39") (class "Default")
      (node (ref "LIM1") (pin "2") (pinfunction "2_2") (pintype "bidirectional"))
      (node (ref "M7") (pin "20") (pinfunction "20_20") (pintype "passive"))
      (node (ref "MASTER") (pin "D39") (pinfunction "D39_D39") (pintype "bidirectional"))
    )
    (net (code "42") (name "/D40") (class "Default")
      (node (ref "LIM2") (pin "1") (pinfunction "1_1") (pintype "bidirectional"))
      (node (ref "M7") (pin "21") (pinfunction "21_21") (pintype "passive"))
      (node (ref "MASTER") (pin "D40") (pinfunction "D40_D40") (pintype "bidirectional"))
    )
    (net (code "43") (name "/D41") (class "Default")
      (node (ref "LIM2") (pin "2") (pinfunction "2_2") (pintype "bidirectional"))
      (node (ref "M7") (pin "22") (pinfunction "22_22") (pintype "passive"))
      (node (ref "MASTER") (pin "D41") (pinfunction "D41_D41") (pintype "bidirectional"))
    )
    (net (code "44") (name "/D42") (class "Default")
      (node (ref "BUZ-M") (pin "+") (pinfunction "1_+") (pintype "passive"))
      (node (ref "M7") (pin "23") (pinfunction "23_23") (pintype "passive"))
      (node (ref "MASTER") (pin "D42") (pinfunction "D42_D42") (pintype "bidirectional"))
    )
    (net (code "45") (name "/D43") (class "Default")
      (node (ref "M7") (pin "24") (pinfunction "24_24") (pintype "passive"))
      (node (ref "MASTER") (pin "D43") (pinfunction "D43_D43") (pintype "bidirectional"))
      (node (ref "PARALLEL") (pin "8") (pinfunction "8_8") (pintype "passive"))
    )
    (net (code "46") (name "/D44") (class "Default")
      (node (ref "M7") (pin "25") (pinfunction "25_25") (pintype "passive"))
      (node (ref "MASTER") (pin "D44") (pinfunction "D44_D44") (pintype "bidirectional"))
      (node (ref "PARALLEL") (pin "9") (pinfunction "9_9") (pintype "passive"))
    )
    (net (code "47") (name "/D45") (class "Default")
      (node (ref "M7") (pin "26") (pinfunction "26_26") (pintype "passive"))
      (node (ref "MASTER") (pin "D45") (pinfunction "D45_D45") (pintype "bidirectional"))
      (node (ref "PARALLEL") (pin "10") (pinfunction "10_10") (pintype "passive"))
    )
    (net (code "48") (name "/D46") (class "Default")
      (node (ref "M7") (pin "27") (pinfunction "27_27") (pintype "passive"))
      (node (ref "MASTER") (pin "D46") (pinfunction "D46_D46") (pintype "bidirectional"))
      (node (ref "PARALLEL") (pin "11") (pinfunction "11_11") (pintype "passive"))
    )
    (net (code "49") (name "/D47") (class "Default")
      (node (ref "M7") (pin "28") (pinfunction "28_28") (pintype "passive"))
      (node (ref "MASTER") (pin "D47") (pinfunction "D47_D47") (pintype "bidirectional"))
      (node (ref "PARALLEL") (pin "12") (pinfunction "12_12") (pintype "passive"))
    )
    (net (code "50") (name "/D48") (class "Default")
      (node (ref "M7") (pin "29") (pinfunction "29_29") (pintype "passive"))
      (node (ref "MASTER") (pin "D48") (pinfunction "D48_D48") (pintype "bidirectional"))
      (node (ref "PARALLEL") (pin "13") (pinfunction "13_13") (pintype "passive"))
    )
    (net (code "51") (name "/D49") (class "Default")
      (node (ref "M7") (pin "30") (pinfunction "30_30") (pintype "passive"))
      (node (ref "MASTER") (pin "D49") (pinfunction "D49_D49") (pintype "bidirectional"))
      (node (ref "PARALLEL") (pin "14") (pinfunction "14_14") (pintype "passive"))
    )
    (net (code "52") (name "/D50") (class "Default")
      (node (ref "M7") (pin "31") (pinfunction "31_31") (pintype "passive"))
      (node (ref "MASTER") (pin "D50") (pinfunction "D50_D50") (pintype "bidirectional"))
    )
    (net (code "53") (name "/D51") (class "Default")
      (node (ref "M7") (pin "32") (pinfunction "32_32") (pintype "passive"))
      (node (ref "MASTER") (pin "D51") (pinfunction "D51_D51") (pintype "bidirectional"))
    )
    (net (code "54") (name "/D52") (class "Default")
      (node (ref "M7") (pin "33") (pinfunction "33_33") (pintype "passive"))
      (node (ref "MASTER") (pin "D52") (pinfunction "D52_D52") (pintype "bidirectional"))
      (node (ref "R4") (pin "2") (pinfunction "2_2") (pintype "passive"))
    )
    (net (code "55") (name "/D53") (class "Default")
      (node (ref "M7") (pin "34") (pinfunction "34_34") (pintype "passive"))
      (node (ref "MASTER") (pin "D53") (pinfunction "D53_D53") (pintype "bidirectional"))
    )
    (net (code "56") (name "/M-V1") (class "Default")
      (node (ref "M-SOLENOID1") (pin "2") (pinfunction "2_2") (pintype "bidirectional"))
      (node (ref "ULN-MASTER") (pin "16") (pinfunction "16_16") (pintype "passive"))
    )
    (net (code "57") (name "/M-V2") (class "Default")
      (node (ref "M-SOLENOID1") (pin "1") (pinfunction "1_1") (pintype "bidirectional"))
      (node (ref "ULN-MASTER") (pin "15") (pinfunction "15_15") (pintype "passive"))
    )
    (net (code "58") (name "/M-V3") (class "Default")
      (node (ref "M-SOLENOID2") (pin "2") (pinfunction "2_2") (pintype "bidirectional"))
      (node (ref "ULN-MASTER") (pin "14") (pinfunction "14_14") (pintype "passive"))
    )
    (net (code "59") (name "/M-V4") (class "Default")
      (node (ref "M-SOLENOID2") (pin "1") (pinfunction "1_1") (pintype "bidirectional"))
      (node (ref "ULN-MASTER") (pin "13") (pinfunction "13_13") (pintype "passive"))
    )
    (net (code "60") (name "/M-V5") (class "Default")
      (node (ref "M-SOLENOIDS") (pin "3") (pinfunction "3_3") (pintype "bidirectional"))
      (node (ref "ULN-MASTER") (pin "12") (pinfunction "12_12") (pintype "passive"))
    )
    (net (code "61") (name "/M-V6") (class "Default")
      (node (ref "M-SOLENOIDS") (pin "2") (pinfunction "2_2") (pintype "bidirectional"))
      (node (ref "ULN-MASTER") (pin "11") (pinfunction "11_11") (pintype "passive"))
    )
    (net (code "62") (name "/M-V7") (class "Default")
      (node (ref "M-SOLENOIDS") (pin "1") (pinfunction "1_1") (pintype "bidirectional"))
      (node (ref "ULN-MASTER") (pin "10") (pinfunction "10_10") (pintype "passive"))
    )
    (net (code "63") (name "/OUT-M") (class "Default")
      (node (ref "LM358") (pin "1") (pinfunction "1_1") (pintype "passive"))
      (node (ref "LM358") (pin "2") (pinfunction "2_2") (pintype "passive"))
      (node (ref "PPR-M") (pin "2") (pinfunction "2_2") (pintype "passive"))
    )
    (net (code "64") (name "/OUT-S") (class "Default")
      (node (ref "LM358") (pin "6") (pinfunction "6_6") (pintype "passive"))
      (node (ref "LM358") (pin "7") (pinfunction "7_7") (pintype "passive"))
      (node (ref "PPR-S") (pin "2") (pinfunction "2_2") (pintype "passive"))
    )
    (net (code "65") (name "/PPR") (class "Default")
      (node (ref "R3") (pin "1") (pinfunction "1_1") (pintype "passive"))
      (node (ref "S-CYT-PPR") (pin "3") (pinfunction "S_3") (pintype "passive"))
    )
    (net (code "66") (name "/PROX1") (class "Default")
      (node (ref "P1") (pin "2") (pinfunction "2_2") (pintype "bidirectional"))
      (node (ref "U$10") (pin "1") (pinfunction "VIN_1") (pintype "bidirectional"))
    )
    (net (code "67") (name "/PROX2") (class "Default")
      (node (ref "P2") (pin "2") (pinfunction "2_2") (pintype "bidirectional"))
      (node (ref "U$11") (pin "1") (pinfunction "VIN_1") (pintype "bidirectional"))
    )
    (net (code "68") (name "/PROX3") (class "Default")
      (node (ref "P3") (pin "2") (pinfunction "2_2") (pintype "bidirectional"))
      (node (ref "U$13") (pin "1") (pinfunction "VIN_1") (pintype "bidirectional"))
    )
    (net (code "69") (name "/PROX4") (class "Default")
      (node (ref "P4") (pin "2") (pinfunction "2_2") (pintype "bidirectional"))
      (node (ref "U$12") (pin "1") (pinfunction "VIN_1") (pintype "bidirectional"))
    )
    (net (code "70") (name "/RX0") (class "Default")
      (node (ref "M5") (pin "8") (pinfunction "8_8") (pintype "passive"))
      (node (ref "MASTER") (pin "RX0") (pinfunction "RX0_RX0") (pintype "bidirectional"))
      (node (ref "SERIAL") (pin "2") (pinfunction "2_2") (pintype "passive"))
      (node (ref "SHIELD") (pin "RX0") (pinfunction "RX_RX0") (pintype "bidirectional"))
    )
    (net (code "71") (name "/RX1") (class "Default")
      (node (ref "ENC-2") (pin "2") (pinfunction "2_2") (pintype "passive"))
      (node (ref "M-PL") (pin "3") (pinfunction "C3_3") (pintype "passive"))
      (node (ref "M6") (pin "6") (pinfunction "6_6") (pintype "passive"))
      (node (ref "MASTER") (pin "RX1") (pinfunction "RX1_RX1") (pintype "bidirectional"))
    )
    (net (code "72") (name "/S-5V") (class "Default")
      (node (ref "S-ENC-1") (pin "1") (pinfunction "1_1") (pintype "passive"))
      (node (ref "S-ENC-2") (pin "1") (pinfunction "1_1") (pintype "passive"))
      (node (ref "S-PL") (pin "1") (pinfunction "A_1") (pintype "passive"))
      (node (ref "S4") (pin "1") (pinfunction "1_1") (pintype "passive"))
      (node (ref "S4") (pin "2") (pinfunction "2_2") (pintype "passive"))
      (node (ref "SLAVE") (pin "5V1") (pinfunction "5V1_5V1") (pintype "bidirectional"))
      (node (ref "SLAVE") (pin "5V2") (pinfunction "5V2_5V2") (pintype "bidirectional"))
    )
    (net (code "73") (name "/S-A0") (class "Default")
      (node (ref "S6") (pin "1") (pinfunction "1_1") (pintype "passive"))
      (node (ref "SLAVE") (pin "A0") (pinfunction "A0_A0") (pintype "bidirectional"))
    )
    (net (code "74") (name "/S-A1") (class "Default")
      (node (ref "S6") (pin "2") (pinfunction "2_2") (pintype "passive"))
      (node (ref "SLAVE") (pin "A1") (pinfunction "A1_A1") (pintype "bidirectional"))
    )
    (net (code "75") (name "/S-A2") (class "Default")
      (node (ref "S6") (pin "3") (pinfunction "3_3") (pintype "passive"))
      (node (ref "SLAVE") (pin "A2") (pinfunction "A2_A2") (pintype "bidirectional"))
    )
    (net (code "76") (name "/S-A3") (class "Default")
      (node (ref "S6") (pin "4") (pinfunction "4_4") (pintype "passive"))
      (node (ref "SLAVE") (pin "A3") (pinfunction "A3_A3") (pintype "bidirectional"))
    )
    (net (code "77") (name "/S-A4") (class "Default")
      (node (ref "S6") (pin "5") (pinfunction "5_5") (pintype "passive"))
      (node (ref "SLAVE") (pin "A4") (pinfunction "A4_A4") (pintype "bidirectional"))
    )
    (net (code "78") (name "/S-A5") (class "Default")
      (node (ref "S6") (pin "6") (pinfunction "6_6") (pintype "passive"))
      (node (ref "SLAVE") (pin "A5") (pinfunction "A5_A5") (pintype "bidirectional"))
    )
    (net (code "79") (name "/S-A6") (class "Default")
      (node (ref "S6") (pin "7") (pinfunction "7_7") (pintype "passive"))
      (node (ref "SLAVE") (pin "A6") (pinfunction "A6_A6") (pintype "bidirectional"))
    )
    (net (code "80") (name "/S-A7") (class "Default")
      (node (ref "S6") (pin "8") (pinfunction "8_8") (pintype "passive"))
      (node (ref "SLAVE") (pin "A7") (pinfunction "A7_A7") (pintype "bidirectional"))
    )
    (net (code "81") (name "/S-A8") (class "Default")
      (node (ref "S5") (pin "1") (pinfunction "1_1") (pintype "passive"))
      (node (ref "SLAVE") (pin "A8") (pinfunction "A8_A8") (pintype "bidirectional"))
    )
    (net (code "82") (name "/S-A9") (class "Default")
      (node (ref "S5") (pin "2") (pinfunction "2_2") (pintype "passive"))
      (node (ref "SLAVE") (pin "A9") (pinfunction "A9_A9") (pintype "bidirectional"))
    )
    (net (code "83") (name "/S-A10") (class "Default")
      (node (ref "S5") (pin "3") (pinfunction "3_3") (pintype "passive"))
      (node (ref "SLAVE") (pin "A10") (pinfunction "A10_A10") (pintype "bidirectional"))
    )
    (net (code "84") (name "/S-A11") (class "Default")
      (node (ref "S5") (pin "4") (pinfunction "4_4") (pintype "passive"))
      (node (ref "SLAVE") (pin "A11") (pinfunction "A11_A11") (pintype "bidirectional"))
    )
    (net (code "85") (name "/S-A12") (class "Default")
      (node (ref "S5") (pin "5") (pinfunction "5_5") (pintype "passive"))
      (node (ref "SLAVE") (pin "A12") (pinfunction "A12_A12") (pintype "bidirectional"))
    )
    (net (code "86") (name "/S-A13") (class "Default")
      (node (ref "S5") (pin "6") (pinfunction "6_6") (pintype "passive"))
      (node (ref "SLAVE") (pin "A13") (pinfunction "A13_A13") (pintype "bidirectional"))
    )
    (net (code "87") (name "/S-A14") (class "Default")
      (node (ref "S5") (pin "7") (pinfunction "7_7") (pintype "passive"))
      (node (ref "SLAVE") (pin "A14") (pinfunction "A14_A14") (pintype "bidirectional"))
    )
    (net (code "88") (name "/S-A15") (class "Default")
      (node (ref "S5") (pin "8") (pinfunction "8_8") (pintype "passive"))
      (node (ref "SLAVE") (pin "A15") (pinfunction "A15_A15") (pintype "bidirectional"))
    )
    (net (code "89") (name "/S-AREF") (class "Default")
      (node (ref "S1") (pin "8") (pinfunction "8_8") (pintype "passive"))
      (node (ref "SLAVE") (pin "AREF") (pinfunction "AREF_AREF") (pintype "bidirectional"))
    )
    (net (code "90") (name "/S-D8") (class "Default")
      (node (ref "S-CYT-PPR") (pin "2") (pinfunction "P_2") (pintype "passive"))
      (node (ref "S1") (pin "1") (pinfunction "1_1") (pintype "passive"))
      (node (ref "SLAVE") (pin "D8") (pinfunction "D8_D8") (pintype "bidirectional"))
    )
    (net (code "91") (name "/S-D9") (class "Default")
      (node (ref "ODRV-S1") (pin "1") (pinfunction "1_1") (pintype "bidirectional"))
      (node (ref "S1") (pin "2") (pinfunction "2_2") (pintype "passive"))
      (node (ref "SLAVE") (pin "D9") (pinfunction "D9_D9") (pintype "bidirectional"))
    )
    (net (code "92") (name "/S-D13") (class "Default")
      (node (ref "ODRV-S1") (pin "2") (pinfunction "2_2") (pintype "bidirectional"))
      (node (ref "S1") (pin "6") (pinfunction "6_6") (pintype "passive"))
      (node (ref "SLAVE") (pin "D13") (pinfunction "D13_D13") (pintype "bidirectional"))
    )
    (net (code "93") (name "/S-D22") (class "Default")
      (node (ref "S-ENC-1") (pin "3") (pinfunction "3_3") (pintype "passive"))
      (node (ref "S-PL") (pin "4") (pinfunction "C4_4") (pintype "passive"))
      (node (ref "S4") (pin "3") (pinfunction "3_3") (pintype "passive"))
      (node (ref "SLAVE") (pin "D22") (pinfunction "D22_D22") (pintype "bidirectional"))
    )
    (net (code "94") (name "/S-D23") (class "Default")
      (node (ref "S-ENC-2") (pin "3") (pinfunction "3_3") (pintype "passive"))
      (node (ref "S-PL") (pin "2") (pinfunction "C2_2") (pintype "passive"))
      (node (ref "S4") (pin "4") (pinfunction "4_4") (pintype "passive"))
      (node (ref "SLAVE") (pin "D23") (pinfunction "D23_D23") (pintype "bidirectional"))
    )
    (net (code "95") (name "/S-D24") (class "Default")
      (node (ref "S4") (pin "5") (pinfunction "5_5") (pintype "passive"))
      (node (ref "SLAVE") (pin "D24") (pinfunction "D24_D24") (pintype "bidirectional"))
    )
    (net (code "96") (name "/S-D25") (class "Default")
      (node (ref "S4") (pin "6") (pinfunction "6_6") (pintype "passive"))
      (node (ref "SLAVE") (pin "D25") (pinfunction "D25_D25") (pintype "bidirectional"))
    )
    (net (code "97") (name "/S-D27") (class "Default")
      (node (ref "S4") (pin "8") (pinfunction "8_8") (pintype "passive"))
      (node (ref "SLAVE") (pin "D27") (pinfunction "D27_D27") (pintype "bidirectional"))
    )
    (net (code "98") (name "/S-D28") (class "Default")
      (node (ref "S4") (pin "9") (pinfunction "9_9") (pintype "passive"))
      (node (ref "SLAVE") (pin "D28") (pinfunction "D28_D28") (pintype "bidirectional"))
      (node (ref "U$12") (pin "3") (pinfunction "VO_3") (pintype "bidirectional"))
    )
    (net (code "99") (name "/S-D29") (class "Default")
      (node (ref "S4") (pin "10") (pinfunction "10_10") (pintype "passive"))
      (node (ref "SLAVE") (pin "D29") (pinfunction "D29_D29") (pintype "bidirectional"))
      (node (ref "U$13") (pin "3") (pinfunction "VO_3") (pintype "bidirectional"))
    )
    (net (code "100") (name "/S-D30") (class "Default")
      (node (ref "S4") (pin "11") (pinfunction "11_11") (pintype "passive"))
      (node (ref "SLAVE") (pin "D30") (pinfunction "D30_D30") (pintype "bidirectional"))
      (node (ref "ULN-SLAVE") (pin "7") (pinfunction "7_7") (pintype "passive"))
    )
    (net (code "101") (name "/S-D31") (class "Default")
      (node (ref "S4") (pin "12") (pinfunction "12_12") (pintype "passive"))
      (node (ref "SLAVE") (pin "D31") (pinfunction "D31_D31") (pintype "bidirectional"))
      (node (ref "ULN-SLAVE") (pin "6") (pinfunction "6_6") (pintype "passive"))
    )
    (net (code "102") (name "/S-D32") (class "Default")
      (node (ref "S4") (pin "13") (pinfunction "13_13") (pintype "passive"))
      (node (ref "SLAVE") (pin "D32") (pinfunction "D32_D32") (pintype "bidirectional"))
      (node (ref "ULN-SLAVE") (pin "5") (pinfunction "5_5") (pintype "passive"))
    )
    (net (code "103") (name "/S-D33") (class "Default")
      (node (ref "S4") (pin "14") (pinfunction "14_14") (pintype "passive"))
      (node (ref "SLAVE") (pin "D33") (pinfunction "D33_D33") (pintype "bidirectional"))
      (node (ref "ULN-SLAVE") (pin "4") (pinfunction "4_4") (pintype "passive"))
    )
    (net (code "104") (name "/S-D34") (class "Default")
      (node (ref "S4") (pin "15") (pinfunction "15_15") (pintype "passive"))
      (node (ref "SLAVE") (pin "D34") (pinfunction "D34_D34") (pintype "bidirectional"))
      (node (ref "ULN-SLAVE") (pin "3") (pinfunction "3_3") (pintype "passive"))
    )
    (net (code "105") (name "/S-D35") (class "Default")
      (node (ref "S4") (pin "16") (pinfunction "16_16") (pintype "passive"))
      (node (ref "SLAVE") (pin "D35") (pinfunction "D35_D35") (pintype "bidirectional"))
      (node (ref "ULN-SLAVE") (pin "2") (pinfunction "2_2") (pintype "passive"))
    )
    (net (code "106") (name "/S-D36") (class "Default")
      (node (ref "S4") (pin "17") (pinfunction "17_17") (pintype "passive"))
      (node (ref "SLAVE") (pin "D36") (pinfunction "D36_D36") (pintype "bidirectional"))
      (node (ref "ULN-SLAVE") (pin "1") (pinfunction "1_1") (pintype "passive"))
    )
    (net (code "107") (name "/S-D37") (class "Default")
      (node (ref "S4") (pin "18") (pinfunction "18_18") (pintype "passive"))
      (node (ref "SLAVE") (pin "D37") (pinfunction "D37_D37") (pintype "bidirectional"))
    )
    (net (code "108") (name "/S-D38") (class "Default")
      (node (ref "S-LIM1") (pin "1") (pinfunction "1_1") (pintype "bidirectional"))
      (node (ref "S4") (pin "19") (pinfunction "19_19") (pintype "passive"))
      (node (ref "SLAVE") (pin "D38") (pinfunction "D38_D38") (pintype "bidirectional"))
    )
    (net (code "109") (name "/S-D39") (class "Default")
      (node (ref "S-LIM1") (pin "2") (pinfunction "2_2") (pintype "bidirectional"))
      (node (ref "S4") (pin "20") (pinfunction "20_20") (pintype "passive"))
      (node (ref "SLAVE") (pin "D39") (pinfunction "D39_D39") (pintype "bidirectional"))
    )
    (net (code "110") (name "/S-D40") (class "Default")
      (node (ref "S-LIM2") (pin "1") (pinfunction "1_1") (pintype "bidirectional"))
      (node (ref "S4") (pin "21") (pinfunction "21_21") (pintype "passive"))
      (node (ref "SLAVE") (pin "D40") (pinfunction "D40_D40") (pintype "bidirectional"))
    )
    (net (code "111") (name "/S-D41") (class "Default")
      (node (ref "S-LIM2") (pin "2") (pinfunction "2_2") (pintype "bidirectional"))
      (node (ref "S4") (pin "22") (pinfunction "22_22") (pintype "passive"))
      (node (ref "SLAVE") (pin "D41") (pinfunction "D41_D41") (pintype "bidirectional"))
    )
    (net (code "112") (name "/S-D42") (class "Default")
      (node (ref "BUZ-S") (pin "+") (pinfunction "1_+") (pintype "passive"))
      (node (ref "S4") (pin "23") (pinfunction "23_23") (pintype "passive"))
      (node (ref "SLAVE") (pin "D42") (pinfunction "D42_D42") (pintype "bidirectional"))
    )
    (net (code "113") (name "/S-D43") (class "Default")
      (node (ref "PARALLEL") (pin "7") (pinfunction "7_7") (pintype "passive"))
      (node (ref "S4") (pin "24") (pinfunction "24_24") (pintype "passive"))
      (node (ref "SLAVE") (pin "D43") (pinfunction "D43_D43") (pintype "bidirectional"))
    )
    (net (code "114") (name "/S-D44") (class "Default")
      (node (ref "PARALLEL") (pin "6") (pinfunction "6_6") (pintype "passive"))
      (node (ref "S4") (pin "25") (pinfunction "25_25") (pintype "passive"))
      (node (ref "SLAVE") (pin "D44") (pinfunction "D44_D44") (pintype "bidirectional"))
    )
    (net (code "115") (name "/S-D45") (class "Default")
      (node (ref "PARALLEL") (pin "5") (pinfunction "5_5") (pintype "passive"))
      (node (ref "S4") (pin "26") (pinfunction "26_26") (pintype "passive"))
      (node (ref "SLAVE") (pin "D45") (pinfunction "D45_D45") (pintype "bidirectional"))
    )
    (net (code "116") (name "/S-D46") (class "Default")
      (node (ref "PARALLEL") (pin "4") (pinfunction "4_4") (pintype "passive"))
      (node (ref "S4") (pin "27") (pinfunction "27_27") (pintype "passive"))
      (node (ref "SLAVE") (pin "D46") (pinfunction "D46_D46") (pintype "bidirectional"))
    )
    (net (code "117") (name "/S-D47") (class "Default")
      (node (ref "PARALLEL") (pin "3") (pinfunction "3_3") (pintype "passive"))
      (node (ref "S4") (pin "28") (pinfunction "28_28") (pintype "passive"))
      (node (ref "SLAVE") (pin "D47") (pinfunction "D47_D47") (pintype "bidirectional"))
    )
    (net (code "118") (name "/S-D48") (class "Default")
      (node (ref "PARALLEL") (pin "2") (pinfunction "2_2") (pintype "passive"))
      (node (ref "S4") (pin "29") (pinfunction "29_29") (pintype "passive"))
      (node (ref "SLAVE") (pin "D48") (pinfunction "D48_D48") (pintype "bidirectional"))
    )
    (net (code "119") (name "/S-D49") (class "Default")
      (node (ref "PARALLEL") (pin "1") (pinfunction "1_1") (pintype "passive"))
      (node (ref "S4") (pin "30") (pinfunction "30_30") (pintype "passive"))
      (node (ref "SLAVE") (pin "D49") (pinfunction "D49_D49") (pintype "bidirectional"))
    )
    (net (code "120") (name "/S-D52") (class "Default")
      (node (ref "R1") (pin "2") (pinfunction "2_2") (pintype "passive"))
      (node (ref "S4") (pin "33") (pinfunction "33_33") (pintype "passive"))
      (node (ref "SLAVE") (pin "D52") (pinfunction "D52_D52") (pintype "bidirectional"))
    )
    (net (code "121") (name "/S-D53") (class "Default")
      (node (ref "S4") (pin "34") (pinfunction "34_34") (pintype "passive"))
      (node (ref "SLAVE") (pin "D53") (pinfunction "D53_D53") (pintype "bidirectional"))
    )
    (net (code "122") (name "/S-MISO") (class "Default")
      (node (ref "SLAVE") (pin "MISO") (pinfunction "MISO_MISO") (pintype "bidirectional"))
    )
    (net (code "123") (name "/S-MOSI") (class "Default")
      (node (ref "SLAVE") (pin "MOSI") (pinfunction "MOSI_MOSI") (pintype "bidirectional"))
    )
    (net (code "124") (name "/S-RST") (class "Default")
      (node (ref "SLAVE") (pin "RST1") (pinfunction "RST1_RST1") (pintype "bidirectional"))
    )
    (net (code "125") (name "/S-RX0") (class "Default")
      (node (ref "S2") (pin "1") (pinfunction "1_1") (pintype "passive"))
      (node (ref "SERIAL") (pin "4") (pinfunction "4_4") (pintype "passive"))
      (node (ref "SLAVE") (pin "RX0") (pinfunction "RX0_RX0") (pintype "bidirectional"))
    )
    (net (code "126") (name "/S-RX1") (class "Default")
      (node (ref "S-ENC-2") (pin "2") (pinfunction "2_2") (pintype "passive"))
      (node (ref "S-PL") (pin "3") (pinfunction "C3_3") (pintype "passive"))
      (node (ref "S3") (pin "3") (pinfunction "3_3") (pintype "passive"))
      (node (ref "SLAVE") (pin "RX1") (pinfunction "RX1_RX1") (pintype "bidirectional"))
    )
    (net (code "127") (name "/S-SCK") (class "Default")
      (node (ref "SLAVE") (pin "SCK") (pinfunction "SCK_SCK") (pintype "bidirectional"))
    )
    (net (code "128") (name "/S-TX0") (class "Default")
      (node (ref "S2") (pin "2") (pinfunction "2_2") (pintype "passive"))
      (node (ref "SERIAL") (pin "3") (pinfunction "3_3") (pintype "passive"))
      (node (ref "SLAVE") (pin "TX0") (pinfunction "TX0_TX0") (pintype "bidirectional"))
    )
    (net (code "129") (name "/S-TX1") (class "Default")
      (node (ref "S-ENC-1") (pin "2") (pinfunction "2_2") (pintype "passive"))
      (node (ref "S-PL") (pin "5") (pinfunction "C5_5") (pintype "passive"))
      (node (ref "S3") (pin "4") (pinfunction "4_4") (pintype "passive"))
      (node (ref "SLAVE") (pin "TX1") (pinfunction "TX1_TX1") (pintype "bidirectional"))
    )
    (net (code "130") (name "/S-V1") (class "Default")
      (node (ref "S-SOLENOID1") (pin "2") (pinfunction "2_2") (pintype "bidirectional"))
      (node (ref "ULN-SLAVE") (pin "16") (pinfunction "16_16") (pintype "passive"))
    )
    (net (code "131") (name "/S-V2") (class "Default")
      (node (ref "S-SOLENOID1") (pin "1") (pinfunction "1_1") (pintype "bidirectional"))
      (node (ref "ULN-SLAVE") (pin "15") (pinfunction "15_15") (pintype "passive"))
    )
    (net (code "132") (name "/S-V3") (class "Default")
      (node (ref "S-SOLENOID2") (pin "2") (pinfunction "2_2") (pintype "bidirectional"))
      (node (ref "ULN-SLAVE") (pin "14") (pinfunction "14_14") (pintype "passive"))
    )
    (net (code "133") (name "/S-V4") (class "Default")
      (node (ref "S-SOLENOID2") (pin "1") (pinfunction "1_1") (pintype "bidirectional"))
      (node (ref "ULN-SLAVE") (pin "13") (pinfunction "13_13") (pintype "passive"))
    )
    (net (code "134") (name "/S-V5") (class "Default")
      (node (ref "S-SOLENOIDS") (pin "3") (pinfunction "3_3") (pintype "bidirectional"))
      (node (ref "ULN-SLAVE") (pin "12") (pinfunction "12_12") (pintype "passive"))
    )
    (net (code "135") (name "/S-V6") (class "Default")
      (node (ref "S-SOLENOIDS") (pin "2") (pinfunction "2_2") (pintype "bidirectional"))
      (node (ref "ULN-SLAVE") (pin "11") (pinfunction "11_11") (pintype "passive"))
    )
    (net (code "136") (name "/S-V7") (class "Default")
      (node (ref "S-SOLENOIDS") (pin "1") (pinfunction "1_1") (pintype "bidirectional"))
      (node (ref "ULN-SLAVE") (pin "10") (pinfunction "10_10") (pintype "passive"))
    )
    (net (code "137") (name "/S-VREF") (class "Default")
      (node (ref "S7") (pin "2") (pinfunction "2_2") (pintype "passive"))
      (node (ref "SLAVE") (pin "IOREF") (pinfunction "IOREF_IOREF") (pintype "bidirectional"))
    )
    (net (code "138") (name "/SRST") (class "Default")
      (node (ref "RESET") (pin "2") (pinfunction "2_2") (pintype "passive"))
      (node (ref "S7") (pin "3") (pinfunction "3_3") (pintype "passive"))
      (node (ref "SLAVE") (pin "RST") (pinfunction "RST_RST") (pintype "bidirectional"))
    )
    (net (code "139") (name "/TX0") (class "Default")
      (node (ref "M5") (pin "7") (pinfunction "7_7") (pintype "passive"))
      (node (ref "MASTER") (pin "TX0") (pinfunction "TX0_TX0") (pintype "bidirectional"))
      (node (ref "SERIAL") (pin "1") (pinfunction "1_1") (pintype "passive"))
      (node (ref "SHIELD") (pin "TX0") (pinfunction "TX_TX0") (pintype "bidirectional"))
    )
    (net (code "140") (name "/TX1") (class "Default")
      (node (ref "ENC-1") (pin "2") (pinfunction "2_2") (pintype "passive"))
      (node (ref "M-PL") (pin "5") (pinfunction "C5_5") (pintype "passive"))
      (node (ref "M6") (pin "5") (pinfunction "5_5") (pintype "passive"))
      (node (ref "MASTER") (pin "TX1") (pinfunction "TX1_TX1") (pintype "bidirectional"))
    )
    (net (code "141") (name "/VREF") (class "Default")
      (node (ref "M1") (pin "2") (pinfunction "2_2") (pintype "passive"))
      (node (ref "MASTER") (pin "IOREF") (pinfunction "IOREF_IOREF") (pintype "bidirectional"))
      (node (ref "SHIELD") (pin "VREF") (pinfunction "VREF_VREF") (pintype "bidirectional"))
    )
    (net (code "142") (name "5V3") (class "Default")
      (node (ref "SLAVE") (pin "5V3") (pinfunction "5V3_5V3") (pintype "bidirectional"))
    )
    (net (code "143") (name "5VA") (class "Default")
      (node (ref "ENC-1") (pin "1") (pinfunction "1_1") (pintype "passive"))
      (node (ref "ENC-2") (pin "1") (pinfunction "1_1") (pintype "passive"))
      (node (ref "I2C-M1") (pin "4") (pinfunction "4_4") (pintype "bidirectional"))
      (node (ref "I2C-M2") (pin "4") (pinfunction "4_4") (pintype "bidirectional"))
      (node (ref "M-PL") (pin "1") (pinfunction "A_1") (pintype "passive"))
      (node (ref "M1") (pin "5") (pinfunction "5_5") (pintype "passive"))
      (node (ref "M7") (pin "1") (pinfunction "1_1") (pintype "passive"))
      (node (ref "M7") (pin "2") (pinfunction "2_2") (pintype "passive"))
      (node (ref "MASTER") (pin "5V") (pinfunction "5V_5V") (pintype "bidirectional"))
      (node (ref "MASTER") (pin "5V1") (pinfunction "5V1_5V1") (pintype "bidirectional"))
      (node (ref "MASTER") (pin "5V2") (pinfunction "5V2_5V2") (pintype "bidirectional"))
      (node (ref "MASTER") (pin "5V3") (pinfunction "5V3_5V3") (pintype "bidirectional"))
      (node (ref "SERVO-M") (pin "2") (pinfunction "2_2") (pintype "bidirectional"))
      (node (ref "SHIELD") (pin "5V") (pinfunction "5V_5V") (pintype "bidirectional"))
      (node (ref "SHIELD") (pin "5V1") (pinfunction "5V1_5V1") (pintype "bidirectional"))
    )
    (net (code "144") (name "D5") (class "Default")
      (node (ref "M5") (pin "3") (pinfunction "3_3") (pintype "passive"))
      (node (ref "MASTER") (pin "D5") (pinfunction "D5_D5") (pintype "bidirectional"))
      (node (ref "SABM1") (pin "2") (pinfunction "2_2") (pintype "passive"))
      (node (ref "SHIELD") (pin "D5") (pinfunction "D5_D5") (pintype "bidirectional"))
    )
    (net (code "145") (name "D6") (class "Default")
      (node (ref "M5") (pin "2") (pinfunction "2_2") (pintype "passive"))
      (node (ref "MASTER") (pin "D6") (pinfunction "D6_D6") (pintype "bidirectional"))
      (node (ref "SABM2") (pin "2") (pinfunction "2_2") (pintype "passive"))
      (node (ref "SHIELD") (pin "D6") (pinfunction "D6_D6") (pintype "bidirectional"))
    )
    (net (code "146") (name "D7") (class "Default")
      (node (ref "M5") (pin "1") (pinfunction "1_1") (pintype "passive"))
      (node (ref "MASTER") (pin "D7") (pinfunction "D7_D7") (pintype "bidirectional"))
      (node (ref "SABM3") (pin "2") (pinfunction "2_2") (pintype "passive"))
      (node (ref "SHIELD") (pin "D7") (pinfunction "D7_D7") (pintype "bidirectional"))
    )
    (net (code "147") (name "D8") (class "Default")
      (node (ref "CYT-M") (pin "2") (pinfunction "2_2") (pintype "passive"))
      (node (ref "M4") (pin "1") (pinfunction "1_1") (pintype "passive"))
      (node (ref "MASTER") (pin "D8") (pinfunction "D8_D8") (pintype "bidirectional"))
      (node (ref "SHIELD") (pin "D8") (pinfunction "D8_D8") (pintype "bidirectional"))
    )
    (net (code "148") (name "D10") (class "Default")
      (node (ref "M4") (pin "3") (pinfunction "3_3") (pintype "passive"))
      (node (ref "MASTER") (pin "D10") (pinfunction "D10_D10") (pintype "bidirectional"))
      (node (ref "SHIELD") (pin "D10") (pinfunction "D10_D10") (pintype "bidirectional"))
      (node (ref "STEPPER-M") (pin "1") (pinfunction "1_1") (pintype "passive"))
    )
    (net (code "149") (name "D11") (class "Default")
      (node (ref "M4") (pin "4") (pinfunction "4_4") (pintype "passive"))
      (node (ref "MASTER") (pin "D11") (pinfunction "D11_D11") (pintype "bidirectional"))
      (node (ref "SHIELD") (pin "D11") (pinfunction "D11_D11") (pintype "bidirectional"))
      (node (ref "STEPPER-M") (pin "2") (pinfunction "2_2") (pintype "passive"))
    )
    (net (code "150") (name "D12") (class "Default")
      (node (ref "M4") (pin "5") (pinfunction "5_5") (pintype "passive"))
      (node (ref "MASTER") (pin "D12") (pinfunction "D12_D12") (pintype "bidirectional"))
      (node (ref "SERVO-M") (pin "1") (pinfunction "1_1") (pintype "bidirectional"))
      (node (ref "SHIELD") (pin "D12") (pinfunction "D12_D12") (pintype "bidirectional"))
    )
    (net (code "151") (name "D26") (class "Default")
      (node (ref "CYT-M") (pin "3") (pinfunction "3_3") (pintype "passive"))
      (node (ref "M7") (pin "7") (pinfunction "7_7") (pintype "passive"))
      (node (ref "MASTER") (pin "D26") (pinfunction "D26_D26") (pintype "bidirectional"))
    )
    (net (code "152") (name "GND") (class "Default")
      (node (ref "BUZ-M") (pin "-") (pinfunction "2_-") (pintype "passive"))
      (node (ref "BUZ-S") (pin "-") (pinfunction "2_-") (pintype "passive"))
      (node (ref "C1") (pin "2") (pinfunction "2_2") (pintype "passive"))
      (node (ref "C2") (pin "2") (pinfunction "2_2") (pintype "passive"))
      (node (ref "CYT-M") (pin "1") (pinfunction "1_1") (pintype "passive"))
      (node (ref "CYT-S") (pin "1") (pinfunction "1_1") (pintype "passive"))
      (node (ref "DEBUG-M") (pin "K") (pinfunction "C_K") (pintype "passive"))
      (node (ref "DEBUG-S") (pin "K") (pinfunction "C_K") (pintype "passive"))
      (node (ref "ENC-1") (pin "4") (pinfunction "4_4") (pintype "passive"))
      (node (ref "ENC-2") (pin "4") (pinfunction "4_4") (pintype "passive"))
      (node (ref "GNDARRAY") (pin "1") (pinfunction "1_1") (pintype "passive"))
      (node (ref "GNDARRAY") (pin "2") (pinfunction "2_2") (pintype "passive"))
      (node (ref "GNDARRAY") (pin "3") (pinfunction "3_3") (pintype "passive"))
      (node (ref "GNDARRAY") (pin "4") (pinfunction "4_4") (pintype "passive"))
      (node (ref "GNDARRAY") (pin "5") (pinfunction "5_5") (pintype "passive"))
      (node (ref "I2C-M1") (pin "3") (pinfunction "3_3") (pintype "bidirectional"))
      (node (ref "I2C-M2") (pin "3") (pinfunction "3_3") (pintype "bidirectional"))
      (node (ref "I2C-S1") (pin "3") (pinfunction "3_3") (pintype "bidirectional"))
      (node (ref "I2C-S2") (pin "3") (pinfunction "3_3") (pintype "bidirectional"))
      (node (ref "LIM1") (pin "3") (pinfunction "3_3") (pintype "bidirectional"))
      (node (ref "LIM2") (pin "3") (pinfunction "3_3") (pintype "bidirectional"))
      (node (ref "LM358") (pin "4") (pinfunction "4_4") (pintype "passive"))
      (node (ref "M1") (pin "6") (pinfunction "6_6") (pintype "passive"))
      (node (ref "M1") (pin "7") (pinfunction "7_7") (pintype "passive"))
      (node (ref "M4") (pin "7") (pinfunction "7_7") (pintype "passive"))
      (node (ref "M7") (pin "35") (pinfunction "35_35") (pintype "passive"))
      (node (ref "M7") (pin "36") (pinfunction "36_36") (pintype "passive"))
      (node (ref "MASTER") (pin "GD3") (pinfunction "GD3_GD3") (pintype "bidirectional"))
      (node (ref "MASTER") (pin "GD4") (pinfunction "GD4_GD4") (pintype "bidirectional"))
      (node (ref "MASTER") (pin "GND") (pinfunction "GND_GND") (pintype "bidirectional"))
      (node (ref "MASTER") (pin "GND1") (pinfunction "GND1_GND1") (pintype "bidirectional"))
      (node (ref "MASTER") (pin "GND2") (pinfunction "GND2_GND2") (pintype "bidirectional"))
      (node (ref "MASTER") (pin "GND5") (pinfunction "GND5_GND5") (pintype "bidirectional"))
      (node (ref "NRF_SLAVE") (pin "1") (pinfunction "1_1") (pintype "passive"))
      (node (ref "ODRV-M1") (pin "3") (pinfunction "3_3") (pintype "bidirectional"))
      (node (ref "ODRV-M2") (pin "3") (pinfunction "3_3") (pintype "bidirectional"))
      (node (ref "ODRV-M3") (pin "3") (pinfunction "3_3") (pintype "bidirectional"))
      (node (ref "ODRV-S1") (pin "3") (pinfunction "3_3") (pintype "bidirectional"))
      (node (ref "ODRV-S2") (pin "3") (pinfunction "3_3") (pintype "bidirectional"))
      (node (ref "ODRV-S3") (pin "3") (pinfunction "3_3") (pintype "bidirectional"))
      (node (ref "P1") (pin "1") (pinfunction "1_1") (pintype "bidirectional"))
      (node (ref "P2") (pin "1") (pinfunction "1_1") (pintype "bidirectional"))
      (node (ref "P3") (pin "1") (pinfunction "1_1") (pintype "bidirectional"))
      (node (ref "P4") (pin "1") (pinfunction "1_1") (pintype "bidirectional"))
      (node (ref "PPR-M") (pin "1") (pinfunction "1_1") (pintype "passive"))
      (node (ref "PPR-S") (pin "3") (pinfunction "3_3") (pintype "passive"))
      (node (ref "RESET") (pin "3") (pinfunction "3_3") (pintype "passive"))
      (node (ref "RESET") (pin "4") (pinfunction "4_4") (pintype "passive"))
      (node (ref "S-ENC-1") (pin "4") (pinfunction "4_4") (pintype "passive"))
      (node (ref "S-ENC-2") (pin "4") (pinfunction "4_4") (pintype "passive"))
      (node (ref "S-LIM1") (pin "3") (pinfunction "3_3") (pintype "bidirectional"))
      (node (ref "S-LIM2") (pin "3") (pinfunction "3_3") (pintype "bidirectional"))
      (node (ref "S1") (pin "7") (pinfunction "7_7") (pintype "passive"))
      (node (ref "S4") (pin "35") (pinfunction "35_35") (pintype "passive"))
      (node (ref "S4") (pin "36") (pinfunction "36_36") (pintype "passive"))
      (node (ref "S7") (pin "6") (pinfunction "6_6") (pintype "passive"))
      (node (ref "S7") (pin "7") (pinfunction "7_7") (pintype "passive"))
      (node (ref "SABM1") (pin "1") (pinfunction "1_1") (pintype "passive"))
      (node (ref "SABM2") (pin "1") (pinfunction "1_1") (pintype "passive"))
      (node (ref "SABM3") (pin "1") (pinfunction "1_1") (pintype "passive"))
      (node (ref "SABS1") (pin "1") (pinfunction "1_1") (pintype "passive"))
      (node (ref "SABS2") (pin "1") (pinfunction "1_1") (pintype "passive"))
      (node (ref "SABS3") (pin "1") (pinfunction "1_1") (pintype "passive"))
      (node (ref "SERVO-M") (pin "3") (pinfunction "3_3") (pintype "bidirectional"))
      (node (ref "SERVO-S") (pin "3") (pinfunction "3_3") (pintype "bidirectional"))
      (node (ref "SHIELD") (pin "GND") (pinfunction "GND_GND") (pintype "bidirectional"))
      (node (ref "SHIELD") (pin "GND1") (pinfunction "GD_GND1") (pintype "bidirectional"))
      (node (ref "SHIELD") (pin "GND2") (pinfunction "GND2_GND2") (pintype "bidirectional"))
      (node (ref "SHIELD") (pin "GND3") (pinfunction "GND3_GND3") (pintype "bidirectional"))
      (node (ref "SLAVE") (pin "GD3") (pinfunction "GD3_GD3") (pintype "bidirectional"))
      (node (ref "SLAVE") (pin "GD4") (pinfunction "GD4_GD4") (pintype "bidirectional"))
      (node (ref "SLAVE") (pin "GND") (pinfunction "GND_GND") (pintype "bidirectional"))
      (node (ref "SLAVE") (pin "GND1") (pinfunction "GND1_GND1") (pintype "bidirectional"))
      (node (ref "SLAVE") (pin "GND2") (pinfunction "GND2_GND2") (pintype "bidirectional"))
      (node (ref "SLAVE") (pin "GND5") (pinfunction "GND5_GND5") (pintype "bidirectional"))
      (node (ref "STEPPER-M") (pin "3") (pinfunction "3_3") (pintype "passive"))
      (node (ref "STEPPER-M") (pin "4") (pinfunction "4_4") (pintype "passive"))
      (node (ref "STEPPER-S") (pin "3") (pinfunction "3_3") (pintype "passive"))
      (node (ref "STEPPER-S") (pin "4") (pinfunction "4_4") (pintype "passive"))
      (node (ref "U$10") (pin "2") (pinfunction "GND_2") (pintype "bidirectional"))
      (node (ref "U$11") (pin "2") (pinfunction "GND_2") (pintype "bidirectional"))
      (node (ref "U$12") (pin "2") (pinfunction "GND_2") (pintype "bidirectional"))
      (node (ref "U$13") (pin "2") (pinfunction "GND_2") (pintype "bidirectional"))
      (node (ref "U$2") (pin "2") (pinfunction "2_2") (pintype "bidirectional"))
      (node (ref "U$3") (pin "IN-") (pinfunction "IN-_IN-") (pintype "bidirectional"))
      (node (ref "U$3") (pin "OUT-") (pinfunction "OUT-_OUT-") (pintype "bidirectional"))
      (node (ref "ULN-MASTER") (pin "8") (pinfunction "8_8") (pintype "passive"))
      (node (ref "ULN-SLAVE") (pin "8") (pinfunction "8_8") (pintype "passive"))
    )
    (net (code "153") (name "GND-A") (class "Default")
      (node (ref "U$2") (pin "1") (pinfunction "1_1") (pintype "bidirectional"))
      (node (ref "VCC") (pin "2") (pinfunction "2_2") (pintype "bidirectional"))
    )
    (net (code "154") (name "IRQ") (class "Default")
      (node (ref "NRF_SLAVE") (pin "8") (pinfunction "8_8") (pintype "passive"))
    )
    (net (code "155") (name "MISO") (class "Default")
      (node (ref "MASTER") (pin "MISO") (pinfunction "MISO_MISO") (pintype "bidirectional"))
      (node (ref "SHIELD") (pin "MISO") (pinfunction "MI_MISO") (pintype "bidirectional"))
    )
    (net (code "156") (name "MOSI") (class "Default")
      (node (ref "MASTER") (pin "MOSI") (pinfunction "MOSI_MOSI") (pintype "bidirectional"))
      (node (ref "SHIELD") (pin "MOSI") (pinfunction "MO_MOSI") (pintype "bidirectional"))
    )
    (net (code "157") (name "Net-(C1-Pad1)") (class "Default")
      (node (ref "C1") (pin "1") (pinfunction "1_1") (pintype "passive"))
      (node (ref "LM358") (pin "3") (pinfunction "3_3") (pintype "passive"))
      (node (ref "R2") (pin "1") (pinfunction "1_1") (pintype "passive"))
    )
    (net (code "158") (name "Net-(C2-Pad1)") (class "Default")
      (node (ref "C2") (pin "1") (pinfunction "1_1") (pintype "passive"))
      (node (ref "LM358") (pin "5") (pinfunction "5_5") (pintype "passive"))
      (node (ref "R3") (pin "2") (pinfunction "2_2") (pintype "passive"))
    )
    (net (code "159") (name "Net-(DEBUG-M-PadA)") (class "Default")
      (node (ref "DEBUG-M") (pin "A") (pinfunction "A_A") (pintype "passive"))
      (node (ref "R4") (pin "1") (pinfunction "1_1") (pintype "passive"))
    )
    (net (code "160") (name "Net-(DEBUG-S-PadA)") (class "Default")
      (node (ref "DEBUG-S") (pin "A") (pinfunction "A_A") (pintype "passive"))
      (node (ref "R1") (pin "1") (pinfunction "1_1") (pintype "passive"))
    )
    (net (code "161") (name "Net-(M1-Pad1)") (class "Default")
      (node (ref "M1") (pin "1") (pinfunction "1_1") (pintype "passive"))
      (node (ref "MASTER") (pin "-") (pinfunction "-_-") (pintype "bidirectional"))
    )
    (net (code "162") (name "Net-(S7-Pad1)") (class "Default")
      (node (ref "S7") (pin "1") (pinfunction "1_1") (pintype "passive"))
      (node (ref "SLAVE") (pin "-") (pinfunction "-_-") (pintype "bidirectional"))
    )
    (net (code "163") (name "RST") (class "Default")
      (node (ref "M1") (pin "3") (pinfunction "3_3") (pintype "passive"))
      (node (ref "MASTER") (pin "RST") (pinfunction "RST_RST") (pintype "bidirectional"))
      (node (ref "MASTER") (pin "RST1") (pinfunction "RST1_RST1") (pintype "bidirectional"))
      (node (ref "RESET") (pin "1") (pinfunction "1_1") (pintype "passive"))
      (node (ref "SHIELD") (pin "RST") (pinfunction "RST_RST") (pintype "bidirectional"))
      (node (ref "SHIELD") (pin "RST1") (pinfunction "RST1_RST1") (pintype "bidirectional"))
    )
    (net (code "164") (name "RX2") (class "Default")
      (node (ref "M6") (pin "4") (pinfunction "4_4") (pintype "passive"))
      (node (ref "MASTER") (pin "RX2") (pinfunction "RX2_RX2") (pintype "bidirectional"))
      (node (ref "ODRV-M2") (pin "1") (pinfunction "1_1") (pintype "bidirectional"))
    )
    (net (code "165") (name "RX3") (class "Default")
      (node (ref "M6") (pin "2") (pinfunction "2_2") (pintype "passive"))
      (node (ref "MASTER") (pin "RX3") (pinfunction "RX3_RX3") (pintype "bidirectional"))
      (node (ref "ODRV-M3") (pin "1") (pinfunction "1_1") (pintype "bidirectional"))
    )
    (net (code "166") (name "S-3V3") (class "Default")
      (node (ref "NRF_SLAVE") (pin "2") (pinfunction "2_2") (pintype "passive"))
      (node (ref "S7") (pin "4") (pinfunction "4_4") (pintype "passive"))
      (node (ref "SLAVE") (pin "3V3") (pinfunction "3V3_3V3") (pintype "bidirectional"))
    )
    (net (code "167") (name "S-5VA") (class "Default")
      (node (ref "I2C-S1") (pin "4") (pinfunction "4_4") (pintype "bidirectional"))
      (node (ref "I2C-S2") (pin "4") (pinfunction "4_4") (pintype "bidirectional"))
      (node (ref "S7") (pin "5") (pinfunction "5_5") (pintype "passive"))
      (node (ref "SERVO-S") (pin "2") (pinfunction "2_2") (pintype "bidirectional"))
      (node (ref "SLAVE") (pin "5V") (pinfunction "5V_5V") (pintype "bidirectional"))
    )
    (net (code "168") (name "S-D2") (class "Default")
      (node (ref "NRF_SLAVE") (pin "3") (pinfunction "3_3") (pintype "passive"))
      (node (ref "S2") (pin "3") (pinfunction "3_3") (pintype "passive"))
      (node (ref "SLAVE") (pin "D2") (pinfunction "D2_D2") (pintype "bidirectional"))
    )
    (net (code "169") (name "S-D3") (class "Default")
      (node (ref "NRF_SLAVE") (pin "5") (pinfunction "5_5") (pintype "passive"))
      (node (ref "S2") (pin "4") (pinfunction "4_4") (pintype "passive"))
      (node (ref "SLAVE") (pin "D3") (pinfunction "D3_D3") (pintype "bidirectional"))
    )
    (net (code "170") (name "S-D4") (class "Default")
      (node (ref "NRF_SLAVE") (pin "4") (pinfunction "4_4") (pintype "passive"))
      (node (ref "S2") (pin "5") (pinfunction "5_5") (pintype "passive"))
      (node (ref "SLAVE") (pin "D4") (pinfunction "D4_D4") (pintype "bidirectional"))
    )
    (net (code "171") (name "S-D5") (class "Default")
      (node (ref "S2") (pin "6") (pinfunction "6_6") (pintype "passive"))
      (node (ref "SABS1") (pin "2") (pinfunction "2_2") (pintype "passive"))
      (node (ref "SLAVE") (pin "D5") (pinfunction "D5_D5") (pintype "bidirectional"))
    )
    (net (code "172") (name "S-D6") (class "Default")
      (node (ref "S2") (pin "7") (pinfunction "7_7") (pintype "passive"))
      (node (ref "SABS2") (pin "2") (pinfunction "2_2") (pintype "passive"))
      (node (ref "SLAVE") (pin "D6") (pinfunction "D6_D6") (pintype "bidirectional"))
    )
    (net (code "173") (name "S-D7") (class "Default")
      (node (ref "S2") (pin "8") (pinfunction "8_8") (pintype "passive"))
      (node (ref "SABS3") (pin "2") (pinfunction "2_2") (pintype "passive"))
      (node (ref "SLAVE") (pin "D7") (pinfunction "D7_D7") (pintype "bidirectional"))
    )
    (net (code "174") (name "S-D10") (class "Default")
      (node (ref "S1") (pin "3") (pinfunction "3_3") (pintype "passive"))
      (node (ref "SLAVE") (pin "D10") (pinfunction "D10_D10") (pintype "bidirectional"))
      (node (ref "STEPPER-S") (pin "1") (pinfunction "1_1") (pintype "passive"))
    )
    (net (code "175") (name "S-D11") (class "Default")
      (node (ref "S1") (pin "4") (pinfunction "4_4") (pintype "passive"))
      (node (ref "SLAVE") (pin "D11") (pinfunction "D11_D11") (pintype "bidirectional"))
      (node (ref "STEPPER-S") (pin "2") (pinfunction "2_2") (pintype "passive"))
    )
    (net (code "176") (name "S-D12") (class "Default")
      (node (ref "S1") (pin "5") (pinfunction "5_5") (pintype "passive"))
      (node (ref "SERVO-S") (pin "1") (pinfunction "1_1") (pintype "bidirectional"))
      (node (ref "SLAVE") (pin "D12") (pinfunction "D12_D12") (pintype "bidirectional"))
    )
    (net (code "177") (name "S-D26") (class "Default")
      (node (ref "CYT-S") (pin "3") (pinfunction "3_3") (pintype "passive"))
      (node (ref "S4") (pin "7") (pinfunction "7_7") (pintype "passive"))
      (node (ref "SLAVE") (pin "D26") (pinfunction "D26_D26") (pintype "bidirectional"))
    )
    (net (code "178") (name "S-D50") (class "Default")
      (node (ref "NRF_SLAVE") (pin "6") (pinfunction "6_6") (pintype "passive"))
      (node (ref "S4") (pin "31") (pinfunction "31_31") (pintype "passive"))
      (node (ref "SLAVE") (pin "D50") (pinfunction "D50_D50") (pintype "bidirectional"))
    )
    (net (code "179") (name "S-D51") (class "Default")
      (node (ref "NRF_SLAVE") (pin "7") (pinfunction "7_7") (pintype "passive"))
      (node (ref "S4") (pin "32") (pinfunction "32_32") (pintype "passive"))
      (node (ref "SLAVE") (pin "D51") (pinfunction "D51_D51") (pintype "bidirectional"))
    )
    (net (code "180") (name "S-RX2") (class "Default")
      (node (ref "ODRV-S2") (pin "1") (pinfunction "1_1") (pintype "bidirectional"))
      (node (ref "S3") (pin "5") (pinfunction "5_5") (pintype "passive"))
      (node (ref "SLAVE") (pin "RX2") (pinfunction "RX2_RX2") (pintype "bidirectional"))
    )
    (net (code "181") (name "S-RX3") (class "Default")
      (node (ref "ODRV-S3") (pin "1") (pinfunction "1_1") (pintype "bidirectional"))
      (node (ref "S3") (pin "7") (pinfunction "7_7") (pintype "passive"))
      (node (ref "SLAVE") (pin "RX3") (pinfunction "RX3_RX3") (pintype "bidirectional"))
    )
    (net (code "182") (name "S-SCL") (class "Default")
      (node (ref "I2C-S1") (pin "2") (pinfunction "2_2") (pintype "bidirectional"))
      (node (ref "I2C-S2") (pin "2") (pinfunction "2_2") (pintype "bidirectional"))
      (node (ref "S1") (pin "10") (pinfunction "10_10") (pintype "passive"))
      (node (ref "S3") (pin "1") (pinfunction "1_1") (pintype "passive"))
      (node (ref "SLAVE") (pin "SCL") (pinfunction "SCL_SCL") (pintype "bidirectional"))
      (node (ref "SLAVE") (pin "SCLU") (pinfunction "SCLU_SCLU") (pintype "bidirectional"))
    )
    (net (code "183") (name "S-SDA") (class "Default")
      (node (ref "I2C-S1") (pin "1") (pinfunction "1_1") (pintype "bidirectional"))
      (node (ref "I2C-S2") (pin "1") (pinfunction "1_1") (pintype "bidirectional"))
      (node (ref "S1") (pin "9") (pinfunction "9_9") (pintype "passive"))
      (node (ref "S3") (pin "2") (pinfunction "2_2") (pintype "passive"))
      (node (ref "SLAVE") (pin "SDA") (pinfunction "SDA_SDA") (pintype "bidirectional"))
      (node (ref "SLAVE") (pin "SDAU") (pinfunction "SDAU_SDAU") (pintype "bidirectional"))
    )
    (net (code "184") (name "S-TX2") (class "Default")
      (node (ref "ODRV-S2") (pin "2") (pinfunction "2_2") (pintype "bidirectional"))
      (node (ref "S3") (pin "6") (pinfunction "6_6") (pintype "passive"))
      (node (ref "SLAVE") (pin "TX2") (pinfunction "TX2_TX2") (pintype "bidirectional"))
    )
    (net (code "185") (name "S-TX3") (class "Default")
      (node (ref "ODRV-S3") (pin "2") (pinfunction "2_2") (pintype "bidirectional"))
      (node (ref "S3") (pin "8") (pinfunction "8_8") (pintype "passive"))
      (node (ref "SLAVE") (pin "TX3") (pinfunction "TX3_TX3") (pintype "bidirectional"))
    )
    (net (code "186") (name "SCK") (class "Default")
      (node (ref "MASTER") (pin "SCK") (pinfunction "SCK_SCK") (pintype "bidirectional"))
      (node (ref "SHIELD") (pin "SCK") (pinfunction "SC_SCK") (pintype "bidirectional"))
    )
    (net (code "187") (name "SCL") (class "Default")
      (node (ref "I2C-M1") (pin "2") (pinfunction "2_2") (pintype "bidirectional"))
      (node (ref "I2C-M2") (pin "2") (pinfunction "2_2") (pintype "bidirectional"))
      (node (ref "M4") (pin "10") (pinfunction "10_10") (pintype "passive"))
      (node (ref "M6") (pin "8") (pinfunction "8_8") (pintype "passive"))
      (node (ref "MASTER") (pin "SCL") (pinfunction "SCL_SCL") (pintype "bidirectional"))
      (node (ref "MASTER") (pin "SCLU") (pinfunction "SCLU_SCLU") (pintype "bidirectional"))
      (node (ref "SHIELD") (pin "SCL") (pinfunction "SCL_SCL") (pintype "bidirectional"))
    )
    (net (code "188") (name "SDA") (class "Default")
      (node (ref "I2C-M1") (pin "1") (pinfunction "1_1") (pintype "bidirectional"))
      (node (ref "I2C-M2") (pin "1") (pinfunction "1_1") (pintype "bidirectional"))
      (node (ref "M4") (pin "9") (pinfunction "9_9") (pintype "passive"))
      (node (ref "M6") (pin "7") (pinfunction "7_7") (pintype "passive"))
      (node (ref "MASTER") (pin "SDA") (pinfunction "SDA_SDA") (pintype "bidirectional"))
      (node (ref "MASTER") (pin "SDAU") (pinfunction "SDAU_SDAU") (pintype "bidirectional"))
      (node (ref "SHIELD") (pin "SDA") (pinfunction "SDA_SDA") (pintype "bidirectional"))
    )
    (net (code "189") (name "TX2") (class "Default")
      (node (ref "M6") (pin "3") (pinfunction "3_3") (pintype "passive"))
      (node (ref "MASTER") (pin "TX2") (pinfunction "TX2_TX2") (pintype "bidirectional"))
      (node (ref "ODRV-M2") (pin "2") (pinfunction "2_2") (pintype "bidirectional"))
    )
    (net (code "190") (name "TX3") (class "Default")
      (node (ref "M6") (pin "1") (pinfunction "1_1") (pintype "passive"))
      (node (ref "MASTER") (pin "TX3") (pinfunction "TX3_TX3") (pintype "bidirectional"))
      (node (ref "ODRV-M3") (pin "2") (pinfunction "2_2") (pintype "bidirectional"))
    )
    (net (code "191") (name "VCC") (class "Default")
      (node (ref "24V1") (pin "1") (pinfunction "1_1") (pintype "bidirectional"))
      (node (ref "24V1") (pin "2") (pinfunction "2_2") (pintype "bidirectional"))
      (node (ref "24V2") (pin "1") (pinfunction "1_1") (pintype "bidirectional"))
      (node (ref "24V2") (pin "2") (pinfunction "2_2") (pintype "bidirectional"))
      (node (ref "LM358") (pin "8") (pinfunction "8_8") (pintype "passive"))
      (node (ref "P1") (pin "3") (pinfunction "3_3") (pintype "bidirectional"))
      (node (ref "P2") (pin "3") (pinfunction "3_3") (pintype "bidirectional"))
      (node (ref "P3") (pin "3") (pinfunction "3_3") (pintype "bidirectional"))
      (node (ref "P4") (pin "3") (pinfunction "3_3") (pintype "bidirectional"))
      (node (ref "PPR-M") (pin "3") (pinfunction "3_3") (pintype "passive"))
      (node (ref "PPR-S") (pin "1") (pinfunction "1_1") (pintype "passive"))
      (node (ref "U$3") (pin "IN+") (pinfunction "IN+_IN+") (pintype "bidirectional"))
      (node (ref "ULN-MASTER") (pin "9") (pinfunction "9_9") (pintype "passive"))
      (node (ref "ULN-SLAVE") (pin "9") (pinfunction "9_9") (pintype "passive"))
      (node (ref "VCC") (pin "1") (pinfunction "1_1") (pintype "bidirectional"))
    )
    (net (code "192") (name "VIN") (class "Default")
      (node (ref "M1") (pin "8") (pinfunction "8_8") (pintype "passive"))
      (node (ref "MASTER") (pin "VIN") (pinfunction "VIN_VIN") (pintype "bidirectional"))
      (node (ref "S7") (pin "8") (pinfunction "8_8") (pintype "passive"))
      (node (ref "SHIELD") (pin "VIN") (pinfunction "VIN_VIN") (pintype "bidirectional"))
      (node (ref "SLAVE") (pin "VIN") (pinfunction "VIN_VIN") (pintype "bidirectional"))
      (node (ref "U$3") (pin "OUT+") (pinfunction "OUT+_OUT+") (pintype "bidirectional"))
    )
    (net (code "193") (name "unconnected-(SHIELD-Pad-)") (class "Default")
      (node (ref "SHIELD") (pin "-") (pinfunction "-_-") (pintype "bidirectional"))
    )
  )
)
